# Rev_1.net
KiCad netlist of a schematic drawn in EAGLE
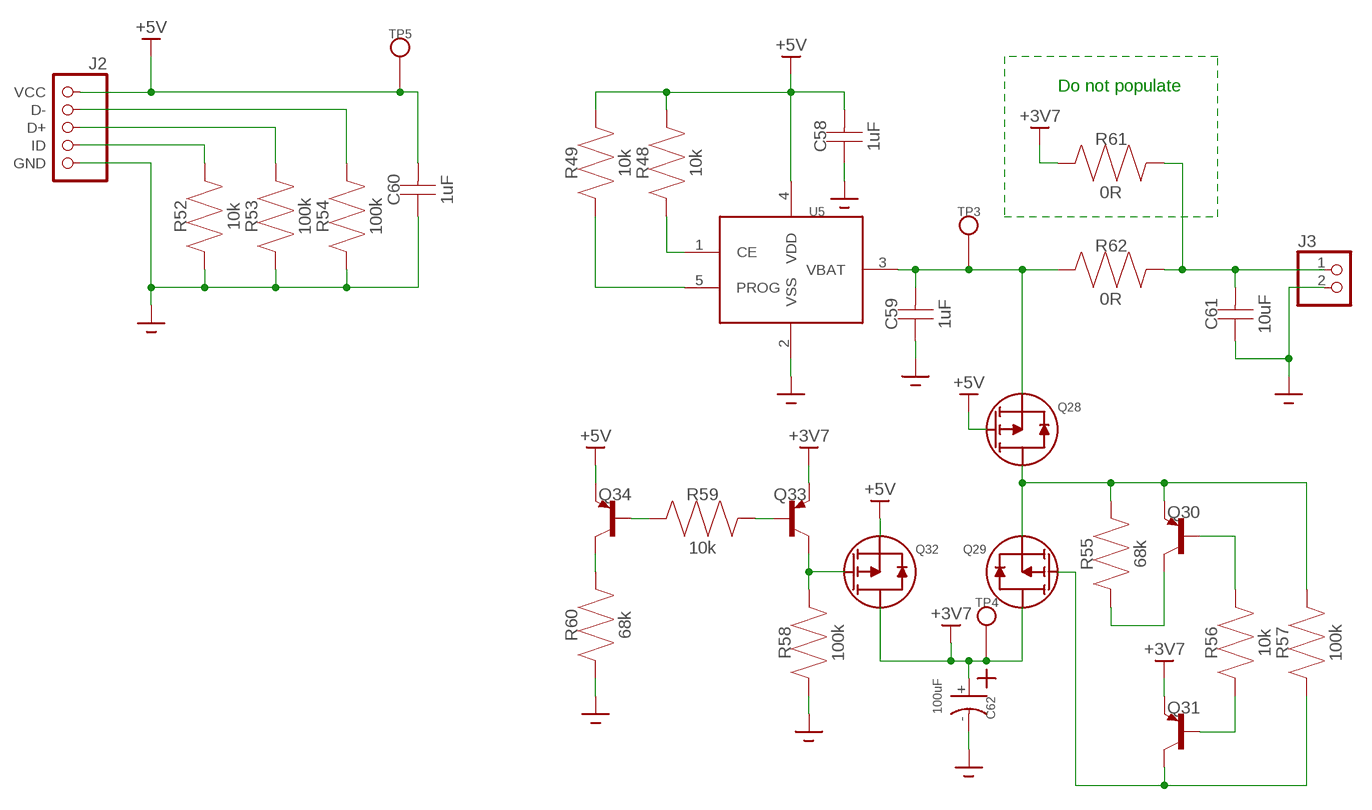
[diagram p0: schematic, sheet 1]
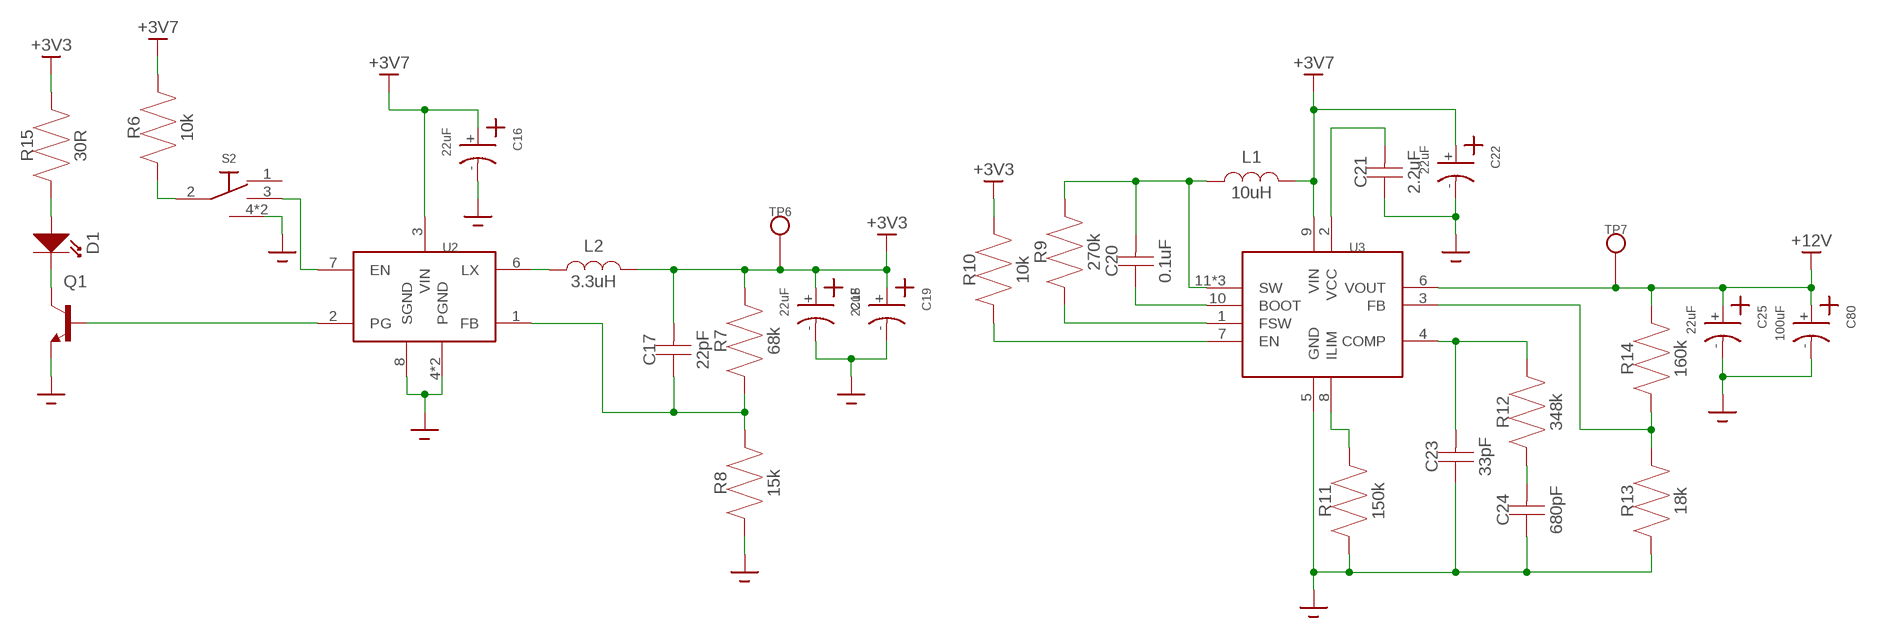
[diagram p1: schematic, sheet 2]
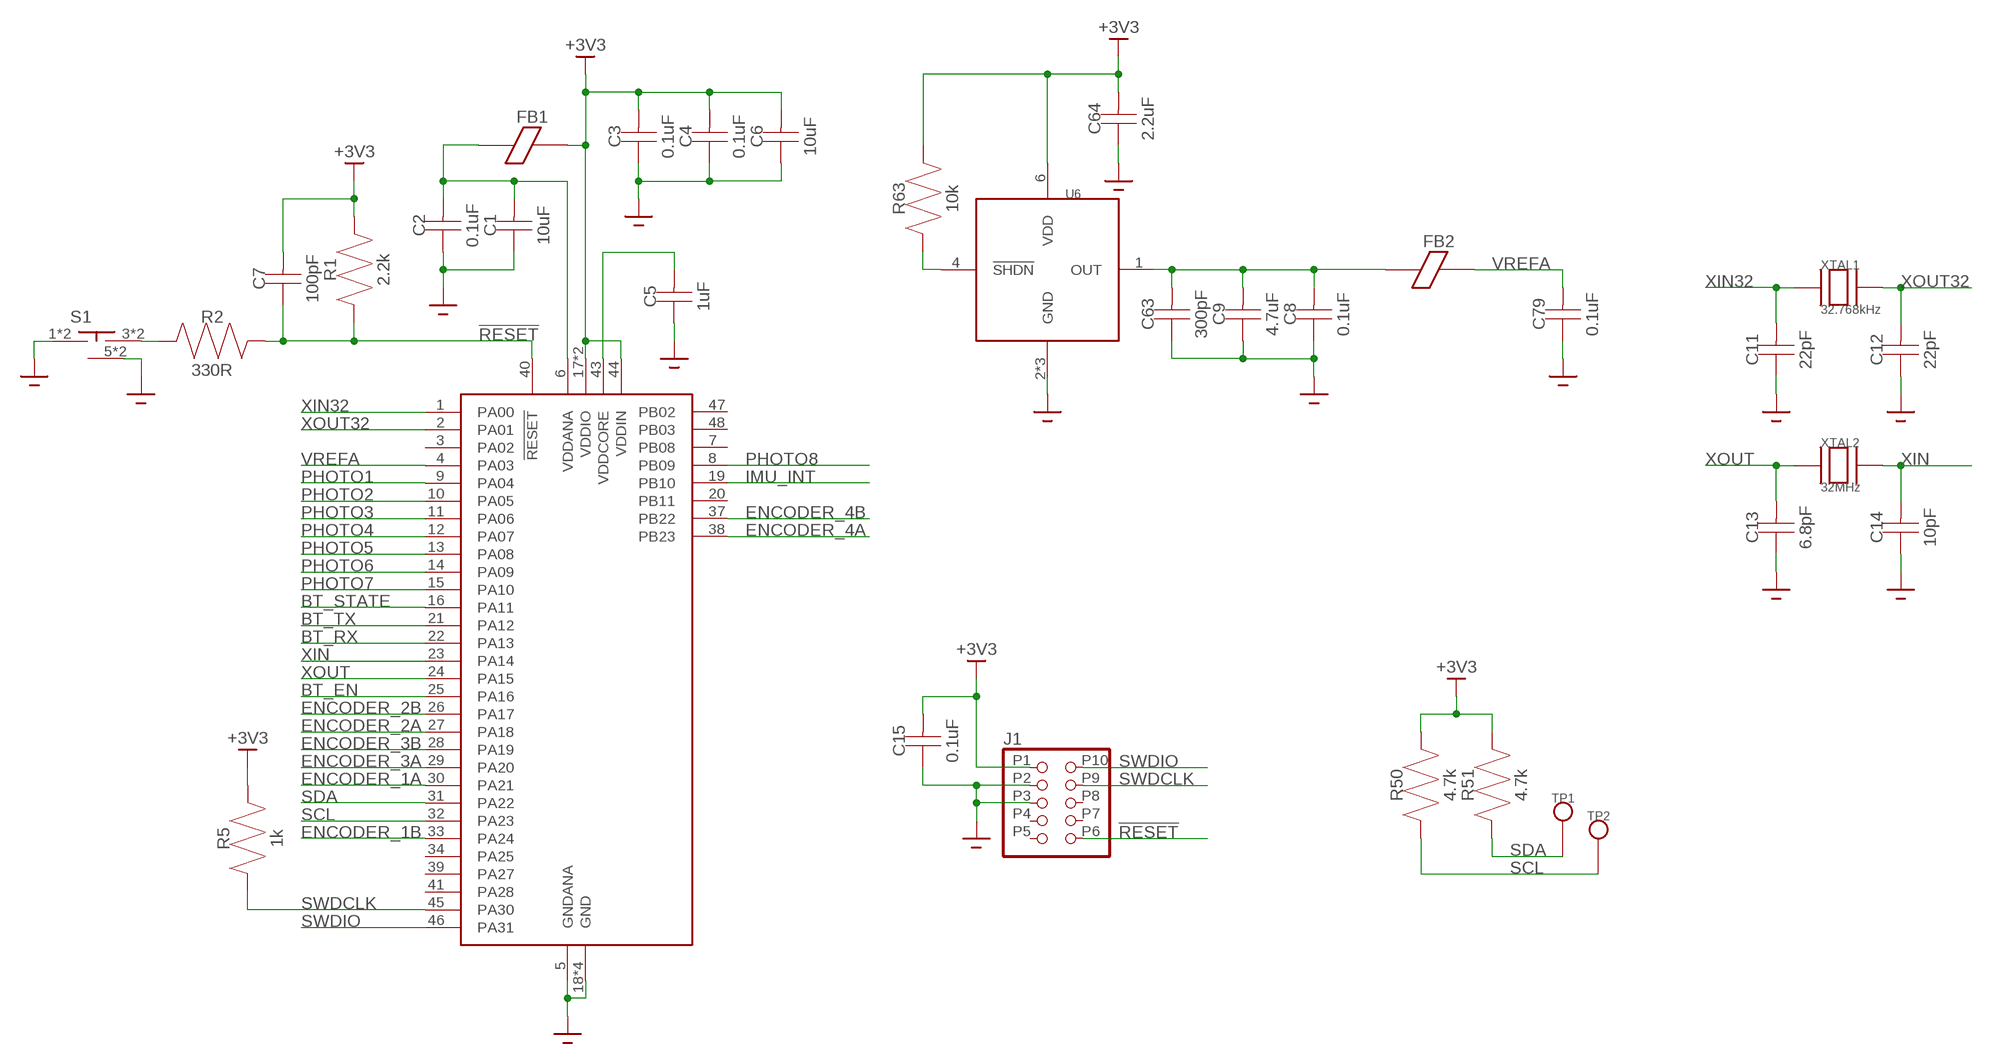
[diagram p2: schematic, sheet 3]
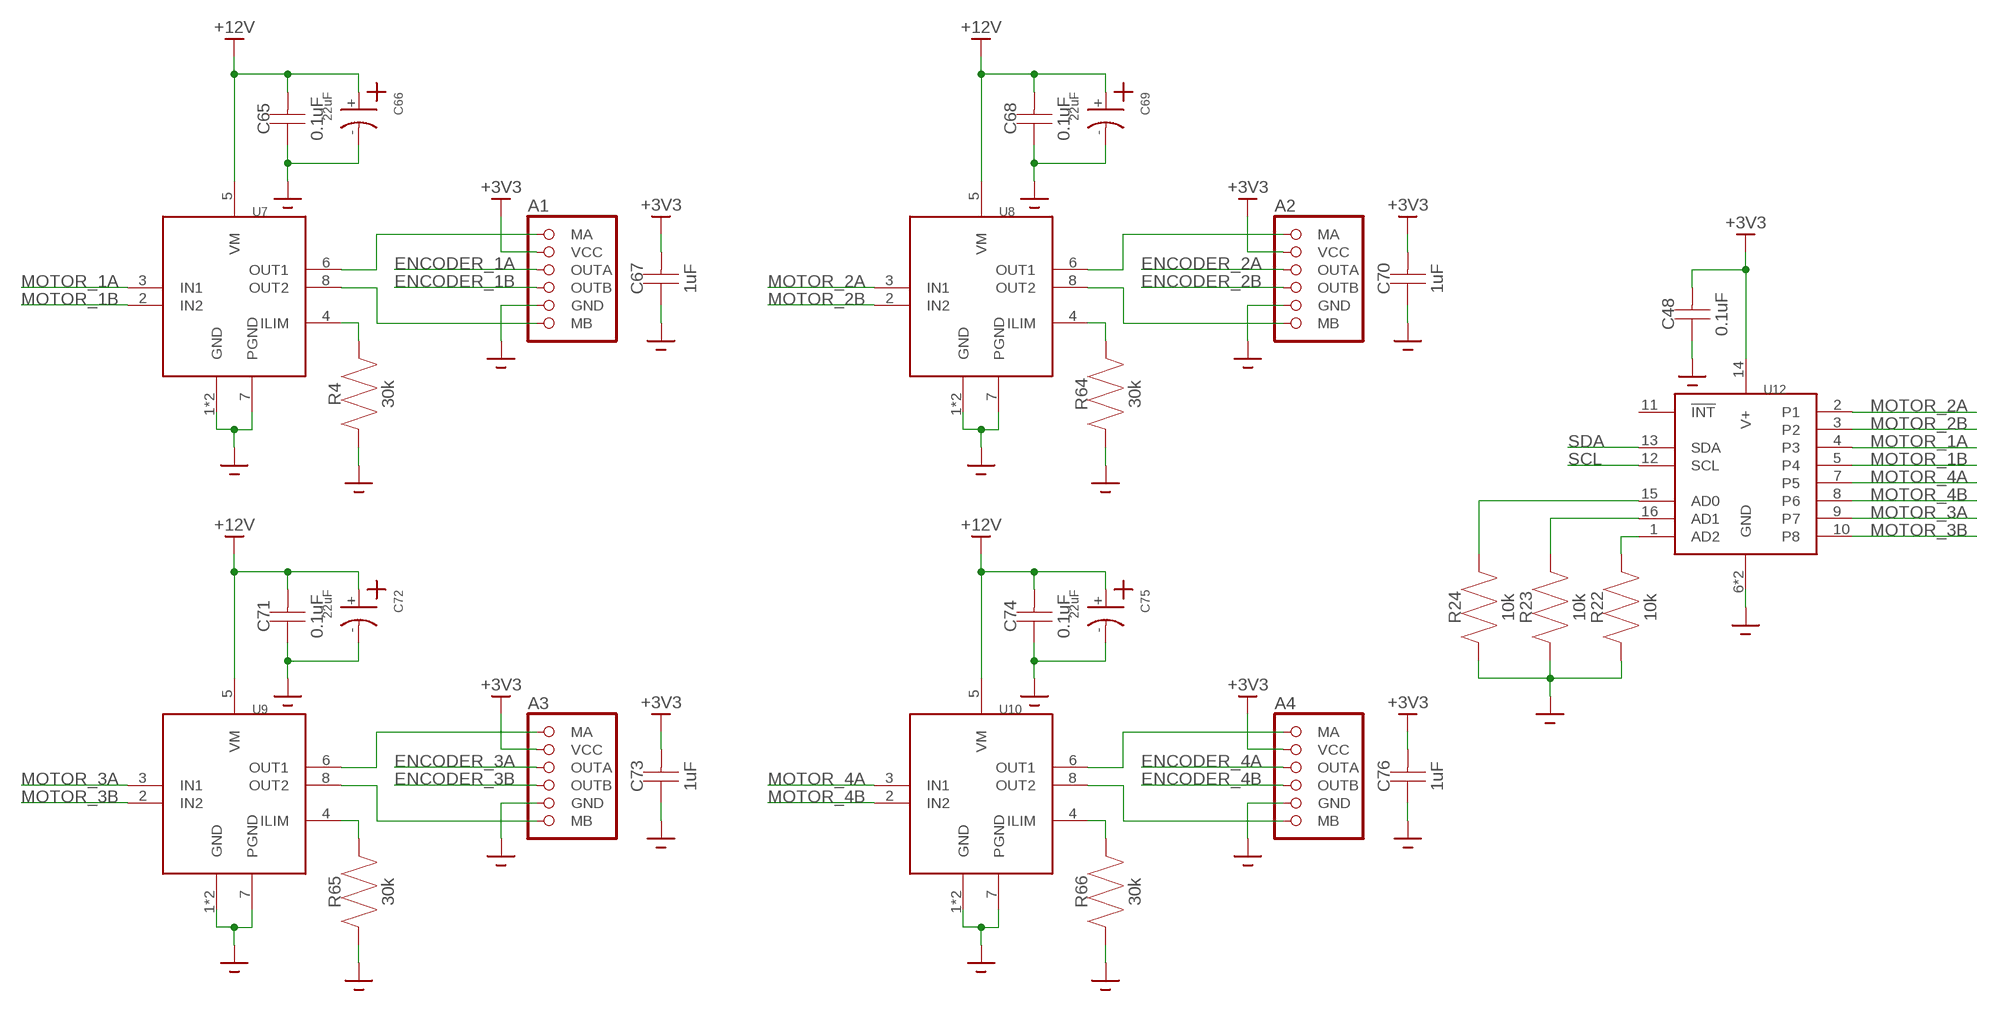
[diagram p3: schematic, sheet 4]
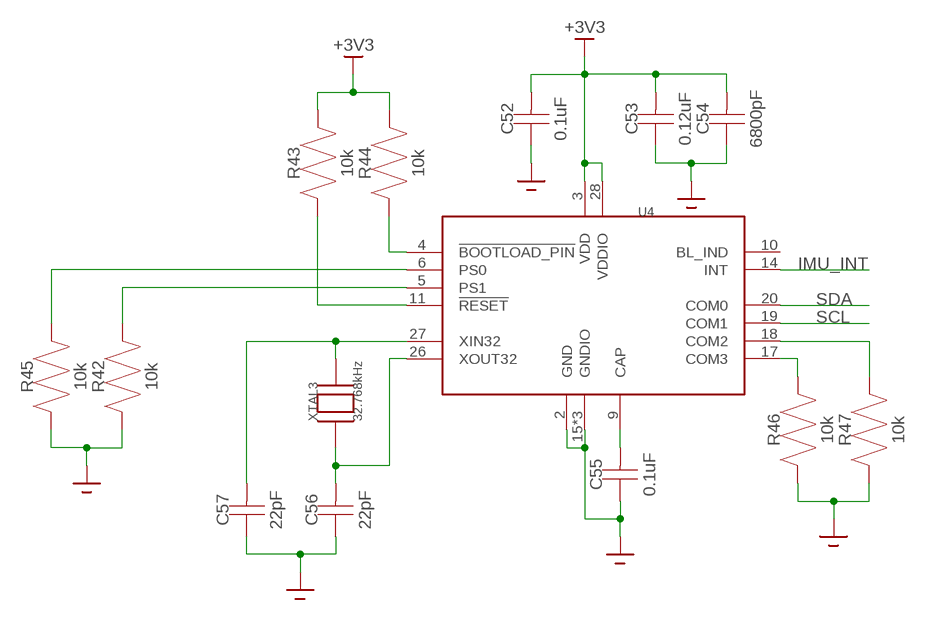
[diagram p4: schematic, sheet 5]
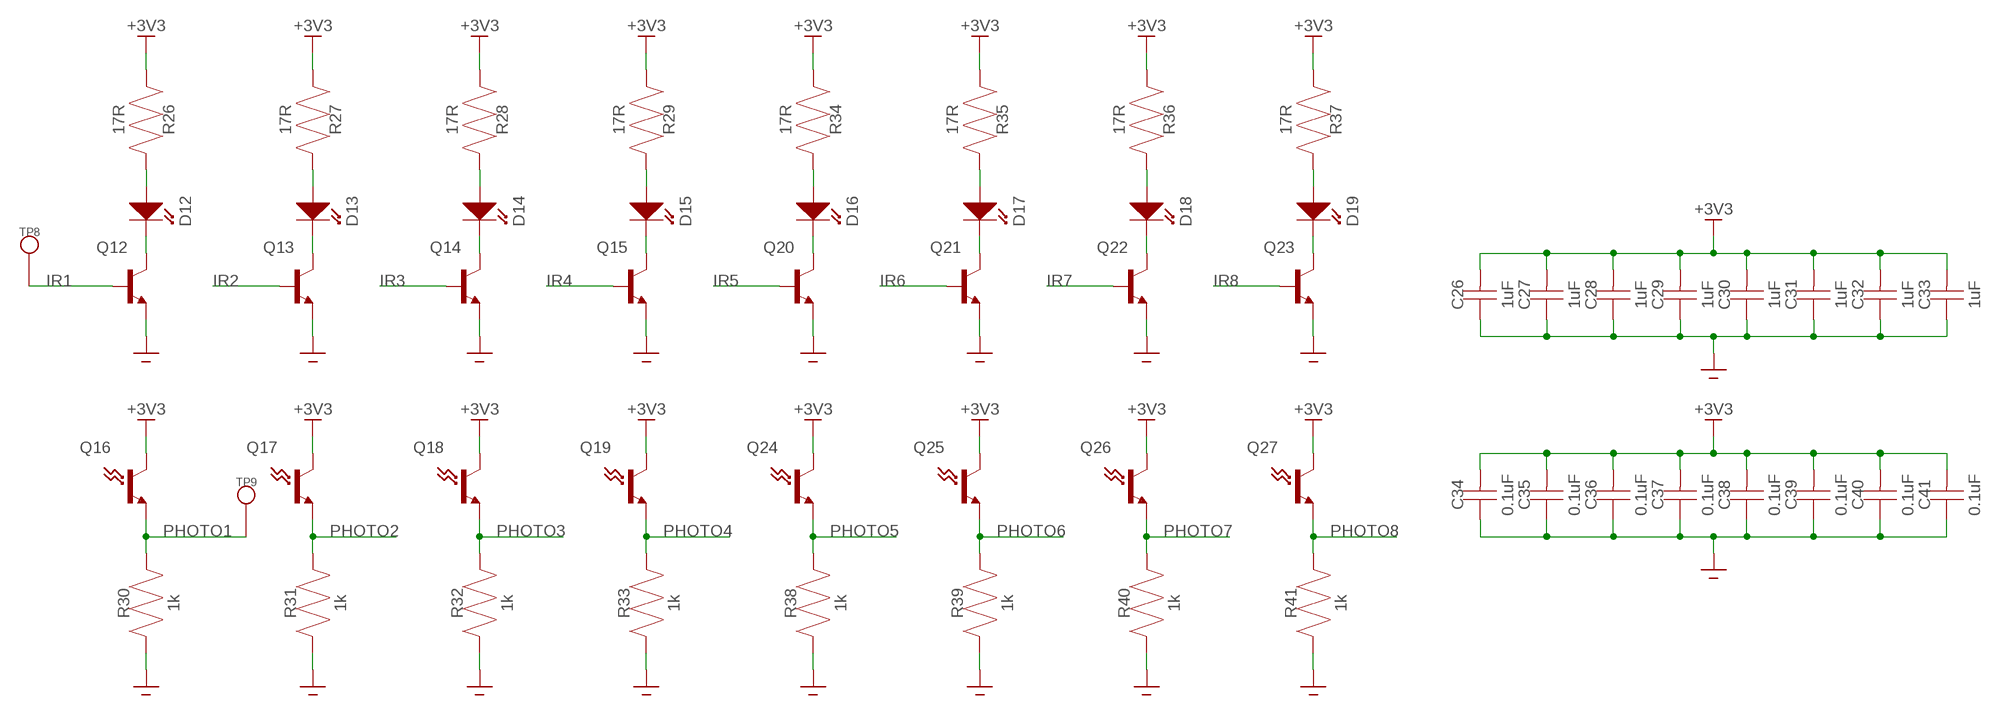
[diagram p5: schematic, sheet 6]
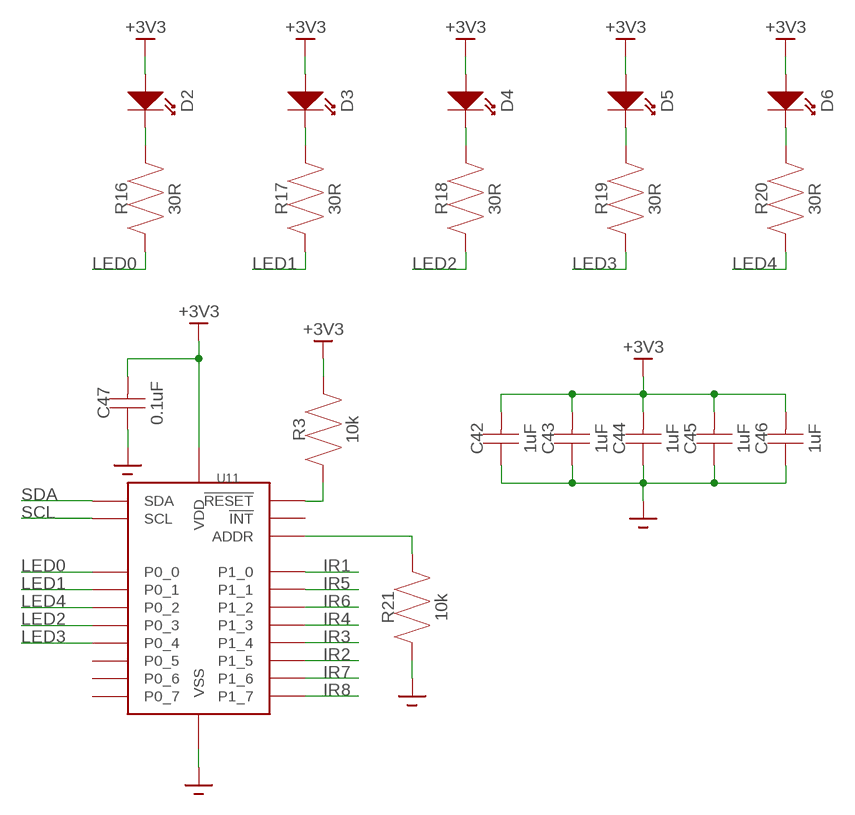
[diagram p6: schematic, sheet 7]
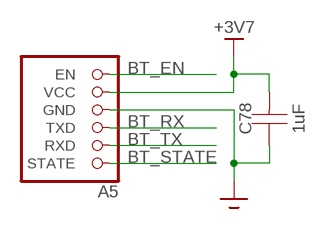
[diagram p7: schematic, sheet 8]

(export (version "E")
  (design (tool "Eeschema 10.0.6"))
  (components
    (comp (ref "C26")
      (value "1uF")
      (footprint "eagle-import:0805")
      (libsource (lib "eagle-import") (part "CAPACITOR0805"))
    )
    (comp (ref "C27")
      (value "1uF")
      (footprint "eagle-import:0805")
      (libsource (lib "eagle-import") (part "CAPACITOR0805"))
    )
    (comp (ref "C28")
      (value "1uF")
      (footprint "eagle-import:0805")
      (libsource (lib "eagle-import") (part "CAPACITOR0805"))
    )
    (comp (ref "C29")
      (value "1uF")
      (footprint "eagle-import:0805")
      (libsource (lib "eagle-import") (part "CAPACITOR0805"))
    )
    (comp (ref "C30")
      (value "1uF")
      (footprint "eagle-import:0805")
      (libsource (lib "eagle-import") (part "CAPACITOR0805"))
    )
    (comp (ref "C31")
      (value "1uF")
      (footprint "eagle-import:0805")
      (libsource (lib "eagle-import") (part "CAPACITOR0805"))
    )
    (comp (ref "C32")
      (value "1uF")
      (footprint "eagle-import:0805")
      (libsource (lib "eagle-import") (part "CAPACITOR0805"))
    )
    (comp (ref "C33")
      (value "1uF")
      (footprint "eagle-import:0603")
      (libsource (lib "eagle-import") (part "CAPACITOR0603"))
    )
    (comp (ref "C34")
      (value "0.1uF")
      (footprint "eagle-import:0805")
      (libsource (lib "eagle-import") (part "CAPACITOR0805"))
    )
    (comp (ref "C35")
      (value "0.1uF")
      (footprint "eagle-import:0805")
      (libsource (lib "eagle-import") (part "CAPACITOR0805"))
    )
    (comp (ref "C36")
      (value "0.1uF")
      (footprint "eagle-import:0805")
      (libsource (lib "eagle-import") (part "CAPACITOR0805"))
    )
    (comp (ref "C37")
      (value "0.1uF")
      (footprint "eagle-import:0805")
      (libsource (lib "eagle-import") (part "CAPACITOR0805"))
    )
    (comp (ref "C38")
      (value "0.1uF")
      (footprint "eagle-import:0805")
      (libsource (lib "eagle-import") (part "CAPACITOR0805"))
    )
    (comp (ref "C39")
      (value "0.1uF")
      (footprint "eagle-import:0805")
      (libsource (lib "eagle-import") (part "CAPACITOR0805"))
    )
    (comp (ref "C40")
      (value "0.1uF")
      (footprint "eagle-import:0603")
      (libsource (lib "eagle-import") (part "CAPACITOR0603"))
    )
    (comp (ref "C41")
      (value "0.1uF")
      (footprint "eagle-import:0805")
      (libsource (lib "eagle-import") (part "CAPACITOR0805"))
    )
    (comp (ref "D12")
      (value "SFH4545")
      (footprint "eagle-import:SFH4545")
      (libsource (lib "eagle-import") (part "SFH4545"))
    )
    (comp (ref "D13")
      (value "SFH4545")
      (footprint "eagle-import:SFH4545")
      (libsource (lib "eagle-import") (part "SFH4545"))
    )
    (comp (ref "D14")
      (value "SFH4545")
      (footprint "eagle-import:SFH4545")
      (libsource (lib "eagle-import") (part "SFH4545"))
    )
    (comp (ref "D15")
      (value "SFH4545")
      (footprint "eagle-import:SFH4545")
      (libsource (lib "eagle-import") (part "SFH4545"))
    )
    (comp (ref "D16")
      (value "SFH4545")
      (footprint "eagle-import:SFH4545")
      (libsource (lib "eagle-import") (part "SFH4545"))
    )
    (comp (ref "D17")
      (value "SFH4545")
      (footprint "eagle-import:SFH4545")
      (libsource (lib "eagle-import") (part "SFH4545"))
    )
    (comp (ref "D18")
      (value "SFH4545")
      (footprint "eagle-import:SFH4545")
      (libsource (lib "eagle-import") (part "SFH4545"))
    )
    (comp (ref "D19")
      (value "SFH4545")
      (footprint "eagle-import:SFH4545")
      (libsource (lib "eagle-import") (part "SFH4545"))
    )
    (comp (ref "Q12")
      (value "MMBT3904,215MMBT3904,215")
      (footprint "eagle-import:SOT95P230X110-3")
      (libsource (lib "eagle-import") (part "MMBT3904,215MMBT3904,215"))
    )
    (comp (ref "Q13")
      (value "MMBT3904,215MMBT3904,215")
      (footprint "eagle-import:SOT95P230X110-3")
      (libsource (lib "eagle-import") (part "MMBT3904,215MMBT3904,215"))
    )
    (comp (ref "Q14")
      (value "MMBT3904,215MMBT3904,215")
      (footprint "eagle-import:SOT95P230X110-3")
      (libsource (lib "eagle-import") (part "MMBT3904,215MMBT3904,215"))
    )
    (comp (ref "Q15")
      (value "MMBT3904,215MMBT3904,215")
      (footprint "eagle-import:SOT95P230X110-3")
      (libsource (lib "eagle-import") (part "MMBT3904,215MMBT3904,215"))
    )
    (comp (ref "Q16")
      (value "TEFT4300")
      (footprint "eagle-import:TEFT4300")
      (libsource (lib "eagle-import") (part "TEFT4300"))
    )
    (comp (ref "Q17")
      (value "TEFT4300")
      (footprint "eagle-import:TEFT4300")
      (libsource (lib "eagle-import") (part "TEFT4300"))
    )
    (comp (ref "Q18")
      (value "TEFT4300")
      (footprint "eagle-import:TEFT4300")
      (libsource (lib "eagle-import") (part "TEFT4300"))
    )
    (comp (ref "Q19")
      (value "TEFT4300")
      (footprint "eagle-import:TEFT4300")
      (libsource (lib "eagle-import") (part "TEFT4300"))
    )
    (comp (ref "Q20")
      (value "MMBT3904,215MMBT3904,215")
      (footprint "eagle-import:SOT95P230X110-3")
      (libsource (lib "eagle-import") (part "MMBT3904,215MMBT3904,215"))
    )
    (comp (ref "Q21")
      (value "MMBT3904,215MMBT3904,215")
      (footprint "eagle-import:SOT95P230X110-3")
      (libsource (lib "eagle-import") (part "MMBT3904,215MMBT3904,215"))
    )
    (comp (ref "Q22")
      (value "MMBT3904,215MMBT3904,215")
      (footprint "eagle-import:SOT95P230X110-3")
      (libsource (lib "eagle-import") (part "MMBT3904,215MMBT3904,215"))
    )
    (comp (ref "Q23")
      (value "MMBT3904,215MMBT3904,215")
      (footprint "eagle-import:SOT95P230X110-3")
      (libsource (lib "eagle-import") (part "MMBT3904,215MMBT3904,215"))
    )
    (comp (ref "Q24")
      (value "TEFT4300")
      (footprint "eagle-import:TEFT4300")
      (libsource (lib "eagle-import") (part "TEFT4300"))
    )
    (comp (ref "Q25")
      (value "TEFT4300")
      (footprint "eagle-import:TEFT4300")
      (libsource (lib "eagle-import") (part "TEFT4300"))
    )
    (comp (ref "Q26")
      (value "TEFT4300")
      (footprint "eagle-import:TEFT4300")
      (libsource (lib "eagle-import") (part "TEFT4300"))
    )
    (comp (ref "Q27")
      (value "TEFT4300")
      (footprint "eagle-import:TEFT4300")
      (libsource (lib "eagle-import") (part "TEFT4300"))
    )
    (comp (ref "R26")
      (value "17R")
      (footprint "eagle-import:0805")
      (libsource (lib "eagle-import") (part "RESISTOR0805"))
    )
    (comp (ref "R27")
      (value "17R")
      (footprint "eagle-import:0805")
      (libsource (lib "eagle-import") (part "RESISTOR0805"))
    )
    (comp (ref "R28")
      (value "17R")
      (footprint "eagle-import:0805")
      (libsource (lib "eagle-import") (part "RESISTOR0805"))
    )
    (comp (ref "R29")
      (value "17R")
      (footprint "eagle-import:0805")
      (libsource (lib "eagle-import") (part "RESISTOR0805"))
    )
    (comp (ref "R30")
      (value "1k")
      (footprint "eagle-import:0805")
      (libsource (lib "eagle-import") (part "RESISTOR0805"))
    )
    (comp (ref "R31")
      (value "1k")
      (footprint "eagle-import:0805")
      (libsource (lib "eagle-import") (part "RESISTOR0805"))
    )
    (comp (ref "R32")
      (value "1k")
      (footprint "eagle-import:0805")
      (libsource (lib "eagle-import") (part "RESISTOR0805"))
    )
    (comp (ref "R33")
      (value "1k")
      (footprint "eagle-import:0805")
      (libsource (lib "eagle-import") (part "RESISTOR0805"))
    )
    (comp (ref "R34")
      (value "17R")
      (footprint "eagle-import:0805")
      (libsource (lib "eagle-import") (part "RESISTOR0805"))
    )
    (comp (ref "R35")
      (value "17R")
      (footprint "eagle-import:0805")
      (libsource (lib "eagle-import") (part "RESISTOR0805"))
    )
    (comp (ref "R36")
      (value "17R")
      (footprint "eagle-import:0805")
      (libsource (lib "eagle-import") (part "RESISTOR0805"))
    )
    (comp (ref "R37")
      (value "17R")
      (footprint "eagle-import:0805")
      (libsource (lib "eagle-import") (part "RESISTOR0805"))
    )
    (comp (ref "R38")
      (value "1k")
      (footprint "eagle-import:0805")
      (libsource (lib "eagle-import") (part "RESISTOR0805"))
    )
    (comp (ref "R39")
      (value "1k")
      (footprint "eagle-import:0805")
      (libsource (lib "eagle-import") (part "RESISTOR0805"))
    )
    (comp (ref "R40")
      (value "1k")
      (footprint "eagle-import:0603")
      (libsource (lib "eagle-import") (part "RESISTOR0603"))
    )
    (comp (ref "R41")
      (value "1k")
      (footprint "eagle-import:0805")
      (libsource (lib "eagle-import") (part "RESISTOR0805"))
    )
    (comp (ref "TP8")
      (value "TESTPOINT")
      (footprint "eagle-import:TESTPOINT")
      (libsource (lib "eagle-import") (part "TESTPOINT"))
    )
    (comp (ref "TP9")
      (value "TESTPOINT")
      (footprint "eagle-import:TESTPOINT")
      (libsource (lib "eagle-import") (part "TESTPOINT"))
    )
    (comp (ref "C1")
      (value "10uF")
      (footprint "eagle-import:0402")
      (libsource (lib "eagle-import") (part "CAPACITOR0402"))
    )
    (comp (ref "C2")
      (value "0.1uF")
      (footprint "eagle-import:0402")
      (libsource (lib "eagle-import") (part "CAPACITOR0402"))
    )
    (comp (ref "C3")
      (value "0.1uF")
      (footprint "eagle-import:0402")
      (libsource (lib "eagle-import") (part "CAPACITOR0402"))
    )
    (comp (ref "C4")
      (value "0.1uF")
      (footprint "eagle-import:0402")
      (libsource (lib "eagle-import") (part "CAPACITOR0402"))
    )
    (comp (ref "C5")
      (value "1uF")
      (footprint "eagle-import:0402")
      (libsource (lib "eagle-import") (part "CAPACITOR0402"))
    )
    (comp (ref "C6")
      (value "10uF")
      (footprint "eagle-import:0402")
      (libsource (lib "eagle-import") (part "CAPACITOR0402"))
    )
    (comp (ref "C7")
      (value "100pF")
      (footprint "eagle-import:0603")
      (libsource (lib "eagle-import") (part "CAPACITOR0603"))
    )
    (comp (ref "C8")
      (value "0.1uF")
      (footprint "eagle-import:0402")
      (libsource (lib "eagle-import") (part "CAPACITOR0402"))
    )
    (comp (ref "C9")
      (value "4.7uF")
      (footprint "eagle-import:0402")
      (libsource (lib "eagle-import") (part "CAPACITOR0402"))
    )
    (comp (ref "C11")
      (value "22pF")
      (footprint "eagle-import:0402")
      (libsource (lib "eagle-import") (part "CAPACITOR0402"))
    )
    (comp (ref "C12")
      (value "22pF")
      (footprint "eagle-import:0402")
      (libsource (lib "eagle-import") (part "CAPACITOR0402"))
    )
    (comp (ref "C13")
      (value "6.8pF")
      (footprint "eagle-import:0402")
      (libsource (lib "eagle-import") (part "CAPACITOR0402"))
    )
    (comp (ref "C14")
      (value "10pF")
      (footprint "eagle-import:0402")
      (libsource (lib "eagle-import") (part "CAPACITOR0402"))
    )
    (comp (ref "C15")
      (value "0.1uF")
      (footprint "eagle-import:0603")
      (libsource (lib "eagle-import") (part "CAPACITOR0603"))
    )
    (comp (ref "C63")
      (value "300pF")
      (footprint "eagle-import:0402")
      (libsource (lib "eagle-import") (part "CAPACITOR0402"))
    )
    (comp (ref "C64")
      (value "2.2uF")
      (footprint "eagle-import:0402")
      (libsource (lib "eagle-import") (part "CAPACITOR0402"))
    )
    (comp (ref "C79")
      (value "0.1uF")
      (footprint "eagle-import:0402")
      (libsource (lib "eagle-import") (part "CAPACITOR0402"))
    )
    (comp (ref "FB1")
      (value "FERRITE0402")
      (footprint "eagle-import:0402")
      (libsource (lib "eagle-import") (part "FERRITE0402"))
    )
    (comp (ref "FB2")
      (value "FERRITE0402")
      (footprint "eagle-import:0402")
      (libsource (lib "eagle-import") (part "FERRITE0402"))
    )
    (comp (ref "J1")
      (value "3220-10-0100-00")
      (footprint "eagle-import:3220-10-0100-00")
      (libsource (lib "eagle-import") (part "3220-10-0100-00"))
    )
    (comp (ref "R1")
      (value "2.2k")
      (footprint "eagle-import:0603")
      (libsource (lib "eagle-import") (part "RESISTOR0603"))
    )
    (comp (ref "R2")
      (value "330R")
      (footprint "eagle-import:0805")
      (libsource (lib "eagle-import") (part "RESISTOR0805"))
    )
    (comp (ref "R5")
      (value "1k")
      (footprint "eagle-import:0603")
      (libsource (lib "eagle-import") (part "RESISTOR0603"))
    )
    (comp (ref "R50")
      (value "4.7k")
      (footprint "eagle-import:0603")
      (libsource (lib "eagle-import") (part "RESISTOR0603"))
    )
    (comp (ref "R51")
      (value "4.7k")
      (footprint "eagle-import:0603")
      (libsource (lib "eagle-import") (part "RESISTOR0603"))
    )
    (comp (ref "R63")
      (value "10k")
      (footprint "eagle-import:0402")
      (libsource (lib "eagle-import") (part "RESISTOR0402"))
    )
    (comp (ref "S1")
      (value "PTS526SMG15SMTR2LFS")
      (footprint "eagle-import:PTS526SMG15SMTR2LFS")
      (libsource (lib "eagle-import") (part "PTS526SMG15SMTR2LFS"))
    )
    (comp (ref "TP1")
      (value "TESTPOINT")
      (footprint "eagle-import:TESTPOINT")
      (libsource (lib "eagle-import") (part "TESTPOINT"))
    )
    (comp (ref "TP2")
      (value "TESTPOINT")
      (footprint "eagle-import:TESTPOINT")
      (libsource (lib "eagle-import") (part "TESTPOINT"))
    )
    (comp (ref "U1")
      (value "ATSAMD21G18A-MU")
      (footprint "eagle-import:ATSAMD21G18A-MU")
      (libsource (lib "eagle-import") (part "ATSAMD21G18A-MU"))
    )
    (comp (ref "U6")
      (value "MCP1501")
      (footprint "eagle-import:MCP1501")
      (libsource (lib "eagle-import") (part "MCP1501"))
    )
    (comp (ref "XTAL1")
      (value "32.768kHz")
      (footprint "eagle-import:FC-135")
      (libsource (lib "eagle-import") (part "FC-135"))
    )
    (comp (ref "XTAL2")
      (value "32MHz")
      (footprint "eagle-import:XRCGB")
      (libsource (lib "eagle-import") (part "XRCGB"))
    )
    (comp (ref "C52")
      (value "0.1uF")
      (footprint "eagle-import:0603")
      (libsource (lib "eagle-import") (part "CAPACITOR0603"))
    )
    (comp (ref "C53")
      (value "0.12uF")
      (footprint "eagle-import:0603")
      (libsource (lib "eagle-import") (part "CAPACITOR0603"))
    )
    (comp (ref "C54")
      (value "6800pF")
      (footprint "eagle-import:0603")
      (libsource (lib "eagle-import") (part "CAPACITOR0603"))
    )
    (comp (ref "C55")
      (value "0.1uF")
      (footprint "eagle-import:0603")
      (libsource (lib "eagle-import") (part "CAPACITOR0603"))
    )
    (comp (ref "C56")
      (value "22pF")
      (footprint "eagle-import:0603")
      (libsource (lib "eagle-import") (part "CAPACITOR0603"))
    )
    (comp (ref "C57")
      (value "22pF")
      (footprint "eagle-import:0603")
      (libsource (lib "eagle-import") (part "CAPACITOR0603"))
    )
    (comp (ref "R42")
      (value "10k")
      (footprint "eagle-import:0603")
      (libsource (lib "eagle-import") (part "RESISTOR0603"))
    )
    (comp (ref "R43")
      (value "10k")
      (footprint "eagle-import:0603")
      (libsource (lib "eagle-import") (part "RESISTOR0603"))
    )
    (comp (ref "R44")
      (value "10k")
      (footprint "eagle-import:0603")
      (libsource (lib "eagle-import") (part "RESISTOR0603"))
    )
    (comp (ref "R45")
      (value "10k")
      (footprint "eagle-import:0603")
      (libsource (lib "eagle-import") (part "RESISTOR0603"))
    )
    (comp (ref "R46")
      (value "10k")
      (footprint "eagle-import:0603")
      (libsource (lib "eagle-import") (part "RESISTOR0603"))
    )
    (comp (ref "R47")
      (value "10k")
      (footprint "eagle-import:0603")
      (libsource (lib "eagle-import") (part "RESISTOR0603"))
    )
    (comp (ref "U4")
      (value "BNO055")
      (footprint "eagle-import:BNO055")
      (libsource (lib "eagle-import") (part "BNO055"))
    )
    (comp (ref "XTAL3")
      (value "32.768kHz")
      (footprint "eagle-import:FC-135")
      (libsource (lib "eagle-import") (part "FC-135"))
    )
    (comp (ref "A1")
      (value "ENCODERSLOT")
      (footprint "eagle-import:ENCODER-SLOT")
      (libsource (lib "eagle-import") (part "ENCODERSLOT"))
    )
    (comp (ref "A2")
      (value "ENCODERSLOT")
      (footprint "eagle-import:ENCODER-SLOT")
      (libsource (lib "eagle-import") (part "ENCODERSLOT"))
    )
    (comp (ref "A3")
      (value "ENCODERSLOT")
      (footprint "eagle-import:ENCODER-SLOT")
      (libsource (lib "eagle-import") (part "ENCODERSLOT"))
    )
    (comp (ref "A4")
      (value "ENCODERSLOT")
      (footprint "eagle-import:ENCODER-SLOT")
      (libsource (lib "eagle-import") (part "ENCODERSLOT"))
    )
    (comp (ref "C48")
      (value "0.1uF")
      (footprint "eagle-import:0603")
      (libsource (lib "eagle-import") (part "CAPACITOR0603"))
    )
    (comp (ref "C65")
      (value "0.1uF")
      (footprint "eagle-import:0805")
      (libsource (lib "eagle-import") (part "CAPACITOR0805"))
    )
    (comp (ref "C66")
      (value "22uF")
      (footprint "eagle-import:865080542006")
      (libsource (lib "eagle-import") (part "865080542006"))
    )
    (comp (ref "C67")
      (value "1uF")
      (footprint "eagle-import:0805")
      (libsource (lib "eagle-import") (part "CAPACITOR0805"))
    )
    (comp (ref "C68")
      (value "0.1uF")
      (footprint "eagle-import:0805")
      (libsource (lib "eagle-import") (part "CAPACITOR0805"))
    )
    (comp (ref "C69")
      (value "22uF")
      (footprint "eagle-import:865080542006")
      (libsource (lib "eagle-import") (part "865080542006"))
    )
    (comp (ref "C70")
      (value "1uF")
      (footprint "eagle-import:0805")
      (libsource (lib "eagle-import") (part "CAPACITOR0805"))
    )
    (comp (ref "C71")
      (value "0.1uF")
      (footprint "eagle-import:0805")
      (libsource (lib "eagle-import") (part "CAPACITOR0805"))
    )
    (comp (ref "C72")
      (value "22uF")
      (footprint "eagle-import:865080542006")
      (libsource (lib "eagle-import") (part "865080542006"))
    )
    (comp (ref "C73")
      (value "1uF")
      (footprint "eagle-import:0805")
      (libsource (lib "eagle-import") (part "CAPACITOR0805"))
    )
    (comp (ref "C74")
      (value "0.1uF")
      (footprint "eagle-import:0805")
      (libsource (lib "eagle-import") (part "CAPACITOR0805"))
    )
    (comp (ref "C75")
      (value "22uF")
      (footprint "eagle-import:865080542006")
      (libsource (lib "eagle-import") (part "865080542006"))
    )
    (comp (ref "C76")
      (value "1uF")
      (footprint "eagle-import:0805")
      (libsource (lib "eagle-import") (part "CAPACITOR0805"))
    )
    (comp (ref "R4")
      (value "30k")
      (footprint "eagle-import:0805")
      (libsource (lib "eagle-import") (part "RESISTOR0805"))
    )
    (comp (ref "R22")
      (value "10k")
      (footprint "eagle-import:0603")
      (libsource (lib "eagle-import") (part "RESISTOR0603"))
    )
    (comp (ref "R23")
      (value "10k")
      (footprint "eagle-import:0603")
      (libsource (lib "eagle-import") (part "RESISTOR0603"))
    )
    (comp (ref "R24")
      (value "10k")
      (footprint "eagle-import:0603")
      (libsource (lib "eagle-import") (part "RESISTOR0603"))
    )
    (comp (ref "R64")
      (value "30k")
      (footprint "eagle-import:0805")
      (libsource (lib "eagle-import") (part "RESISTOR0805"))
    )
    (comp (ref "R65")
      (value "30k")
      (footprint "eagle-import:0805")
      (libsource (lib "eagle-import") (part "RESISTOR0805"))
    )
    (comp (ref "R66")
      (value "30k")
      (footprint "eagle-import:0805")
      (libsource (lib "eagle-import") (part "RESISTOR0805"))
    )
    (comp (ref "U7")
      (value "DRV8871")
      (footprint "eagle-import:DRV8871")
      (libsource (lib "eagle-import") (part "DRV8871"))
    )
    (comp (ref "U8")
      (value "DRV8871")
      (footprint "eagle-import:DRV8871")
      (libsource (lib "eagle-import") (part "DRV8871"))
    )
    (comp (ref "U9")
      (value "DRV8871")
      (footprint "eagle-import:DRV8871")
      (libsource (lib "eagle-import") (part "DRV8871"))
    )
    (comp (ref "U10")
      (value "DRV8871")
      (footprint "eagle-import:DRV8871")
      (libsource (lib "eagle-import") (part "DRV8871"))
    )
    (comp (ref "U12")
      (value "MAX7315")
      (footprint "eagle-import:MAX7315")
      (libsource (lib "eagle-import") (part "MAX7315"))
    )
    (comp (ref "A5")
      (value "HC-05")
      (footprint "eagle-import:HC-05")
      (libsource (lib "eagle-import") (part "HC-05"))
    )
    (comp (ref "C78")
      (value "1uF")
      (footprint "eagle-import:0603")
      (libsource (lib "eagle-import") (part "CAPACITOR0603"))
    )
    (comp (ref "C42")
      (value "1uF")
      (footprint "eagle-import:0603")
      (libsource (lib "eagle-import") (part "CAPACITOR0603"))
    )
    (comp (ref "C43")
      (value "1uF")
      (footprint "eagle-import:0603")
      (libsource (lib "eagle-import") (part "CAPACITOR0603"))
    )
    (comp (ref "C44")
      (value "1uF")
      (footprint "eagle-import:0603")
      (libsource (lib "eagle-import") (part "CAPACITOR0603"))
    )
    (comp (ref "C45")
      (value "1uF")
      (footprint "eagle-import:0603")
      (libsource (lib "eagle-import") (part "CAPACITOR0603"))
    )
    (comp (ref "C46")
      (value "1uF")
      (footprint "eagle-import:0603")
      (libsource (lib "eagle-import") (part "CAPACITOR0603"))
    )
    (comp (ref "C47")
      (value "0.1uF")
      (footprint "eagle-import:0603")
      (libsource (lib "eagle-import") (part "CAPACITOR0603"))
    )
    (comp (ref "D2")
      (value "LED1206")
      (footprint "eagle-import:1206")
      (libsource (lib "eagle-import") (part "LED1206"))
    )
    (comp (ref "D3")
      (value "LED1206")
      (footprint "eagle-import:1206")
      (libsource (lib "eagle-import") (part "LED1206"))
    )
    (comp (ref "D4")
      (value "LED1206")
      (footprint "eagle-import:1206")
      (libsource (lib "eagle-import") (part "LED1206"))
    )
    (comp (ref "D5")
      (value "LED1206")
      (footprint "eagle-import:1206")
      (libsource (lib "eagle-import") (part "LED1206"))
    )
    (comp (ref "D6")
      (value "LED1206")
      (footprint "eagle-import:1206")
      (libsource (lib "eagle-import") (part "LED1206"))
    )
    (comp (ref "R3")
      (value "10k")
      (footprint "eagle-import:0603")
      (libsource (lib "eagle-import") (part "RESISTOR0603"))
    )
    (comp (ref "R16")
      (value "30R")
      (footprint "eagle-import:0603")
      (libsource (lib "eagle-import") (part "RESISTOR0603"))
    )
    (comp (ref "R17")
      (value "30R")
      (footprint "eagle-import:0603")
      (libsource (lib "eagle-import") (part "RESISTOR0603"))
    )
    (comp (ref "R18")
      (value "30R")
      (footprint "eagle-import:0603")
      (libsource (lib "eagle-import") (part "RESISTOR0603"))
    )
    (comp (ref "R19")
      (value "30R")
      (footprint "eagle-import:0603")
      (libsource (lib "eagle-import") (part "RESISTOR0603"))
    )
    (comp (ref "R20")
      (value "30R")
      (footprint "eagle-import:0603")
      (libsource (lib "eagle-import") (part "RESISTOR0603"))
    )
    (comp (ref "R21")
      (value "10k")
      (footprint "eagle-import:0603")
      (libsource (lib "eagle-import") (part "RESISTOR0603"))
    )
    (comp (ref "U11")
      (value "PCAL6416A")
      (footprint "eagle-import:PCAL6416A")
      (libsource (lib "eagle-import") (part "PCAL6416A"))
    )
    (comp (ref "C16")
      (value "22uF")
      (footprint "eagle-import:865080542006")
      (libsource (lib "eagle-import") (part "865080542006"))
    )
    (comp (ref "C17")
      (value "22pF")
      (footprint "eagle-import:0805")
      (libsource (lib "eagle-import") (part "CAPACITOR0805"))
    )
    (comp (ref "C18")
      (value "22uF")
      (footprint "eagle-import:865080542006")
      (libsource (lib "eagle-import") (part "865080542006"))
    )
    (comp (ref "C19")
      (value "22uF")
      (footprint "eagle-import:865080542006")
      (libsource (lib "eagle-import") (part "865080542006"))
    )
    (comp (ref "C20")
      (value "0.1uF")
      (footprint "eagle-import:0402")
      (libsource (lib "eagle-import") (part "CAPACITOR0402"))
    )
    (comp (ref "C21")
      (value "2.2uF")
      (footprint "eagle-import:0402")
      (libsource (lib "eagle-import") (part "CAPACITOR0402"))
    )
    (comp (ref "C22")
      (value "22uF")
      (footprint "eagle-import:865080542006")
      (libsource (lib "eagle-import") (part "865080542006"))
    )
    (comp (ref "C23")
      (value "33pF")
      (footprint "eagle-import:0402")
      (libsource (lib "eagle-import") (part "CAPACITOR0402"))
    )
    (comp (ref "C24")
      (value "680pF")
      (footprint "eagle-import:0402")
      (libsource (lib "eagle-import") (part "CAPACITOR0402"))
    )
    (comp (ref "C25")
      (value "22uF")
      (footprint "eagle-import:865080542006")
      (libsource (lib "eagle-import") (part "865080542006"))
    )
    (comp (ref "C80")
      (value "100uF")
      (footprint "eagle-import:EEE-1EA101AP")
      (libsource (lib "eagle-import") (part "EEE-1EA101AP"))
    )
    (comp (ref "D1")
      (value "LED1206")
      (footprint "eagle-import:1206")
      (libsource (lib "eagle-import") (part "LED1206"))
    )
    (comp (ref "L1")
      (value "10uH")
      (footprint "eagle-import:104CDMCC")
      (libsource (lib "eagle-import") (part "104CDMCC"))
    )
    (comp (ref "L2")
      (value "3.3uH")
      (footprint "eagle-import:NRS5040")
      (libsource (lib "eagle-import") (part "NRS5040"))
    )
    (comp (ref "Q1")
      (value "MMBT3904,215MMBT3904,215")
      (footprint "eagle-import:SOT95P230X110-3")
      (libsource (lib "eagle-import") (part "MMBT3904,215MMBT3904,215"))
    )
    (comp (ref "R6")
      (value "10k")
      (footprint "eagle-import:0805")
      (libsource (lib "eagle-import") (part "RESISTOR0805"))
    )
    (comp (ref "R7")
      (value "68k")
      (footprint "eagle-import:0805")
      (libsource (lib "eagle-import") (part "RESISTOR0805"))
    )
    (comp (ref "R8")
      (value "15k")
      (footprint "eagle-import:0805")
      (libsource (lib "eagle-import") (part "RESISTOR0805"))
    )
    (comp (ref "R9")
      (value "270k")
      (footprint "eagle-import:0402")
      (libsource (lib "eagle-import") (part "RESISTOR0402"))
    )
    (comp (ref "R10")
      (value "10k")
      (footprint "eagle-import:0603")
      (libsource (lib "eagle-import") (part "RESISTOR0603"))
    )
    (comp (ref "R11")
      (value "150k")
      (footprint "eagle-import:0603")
      (libsource (lib "eagle-import") (part "RESISTOR0603"))
    )
    (comp (ref "R12")
      (value "348k")
      (footprint "eagle-import:0402")
      (libsource (lib "eagle-import") (part "RESISTOR0402"))
    )
    (comp (ref "R13")
      (value "18k")
      (footprint "eagle-import:0402")
      (libsource (lib "eagle-import") (part "RESISTOR0402"))
    )
    (comp (ref "R14")
      (value "160k")
      (footprint "eagle-import:0402")
      (libsource (lib "eagle-import") (part "RESISTOR0402"))
    )
    (comp (ref "R15")
      (value "30R")
      (footprint "eagle-import:0805")
      (libsource (lib "eagle-import") (part "RESISTOR0805"))
    )
    (comp (ref "S2")
      (value "OS102011MS2QN1")
      (footprint "eagle-import:OS102011MS2QN1")
      (libsource (lib "eagle-import") (part "OS102011MS2QN1"))
    )
    (comp (ref "TP6")
      (value "TESTPOINT")
      (footprint "eagle-import:TESTPOINT")
      (libsource (lib "eagle-import") (part "TESTPOINT"))
    )
    (comp (ref "TP7")
      (value "TESTPOINT")
      (footprint "eagle-import:TESTPOINT")
      (libsource (lib "eagle-import") (part "TESTPOINT"))
    )
    (comp (ref "U2")
      (value "AP3441")
      (footprint "eagle-import:AP3441")
      (libsource (lib "eagle-import") (part "AP3441"))
    )
    (comp (ref "U3")
      (value "TPS61089")
      (footprint "eagle-import:TPS61089")
      (libsource (lib "eagle-import") (part "TPS61089"))
    )
    (comp (ref "C58")
      (value "1uF")
      (footprint "eagle-import:0805")
      (libsource (lib "eagle-import") (part "CAPACITOR0805"))
    )
    (comp (ref "C59")
      (value "1uF")
      (footprint "eagle-import:0805")
      (libsource (lib "eagle-import") (part "CAPACITOR0805"))
    )
    (comp (ref "C60")
      (value "1uF")
      (footprint "eagle-import:0805")
      (libsource (lib "eagle-import") (part "CAPACITOR0805"))
    )
    (comp (ref "C61")
      (value "10uF")
      (footprint "eagle-import:0805")
      (libsource (lib "eagle-import") (part "CAPACITOR0805"))
    )
    (comp (ref "C62")
      (value "100uF")
      (footprint "eagle-import:EEE-1EA101AP")
      (libsource (lib "eagle-import") (part "EEE-1EA101AP"))
    )
    (comp (ref "J2")
      (value "10118194-0001LF")
      (footprint "eagle-import:10118194-0001LF")
      (libsource (lib "eagle-import") (part "10118194-0001LF"))
    )
    (comp (ref "J3")
      (value "B2B-PH-K-S(LF)(SN)")
      (footprint "eagle-import:B2B-PH-K-S(LF)(SN)")
      (libsource (lib "eagle-import") (part "B2B-PH-K-S(LF)(SN)"))
    )
    (comp (ref "Q28")
      (value "SI7157DP")
      (footprint "eagle-import:SI7157DP")
      (libsource (lib "eagle-import") (part "SI7157DP"))
    )
    (comp (ref "Q29")
      (value "SI7157DP")
      (footprint "eagle-import:SI7157DP")
      (libsource (lib "eagle-import") (part "SI7157DP"))
    )
    (comp (ref "Q30")
      (value "MMBT3906")
      (footprint "eagle-import:SOT96P237X112-3")
      (libsource (lib "eagle-import") (part "MMBT3906"))
    )
    (comp (ref "Q31")
      (value "MMBT3906")
      (footprint "eagle-import:SOT96P237X112-3")
      (libsource (lib "eagle-import") (part "MMBT3906"))
    )
    (comp (ref "Q32")
      (value "SI7157DP")
      (footprint "eagle-import:SI7157DP")
      (libsource (lib "eagle-import") (part "SI7157DP"))
    )
    (comp (ref "Q33")
      (value "MMBT3906")
      (footprint "eagle-import:SOT96P237X112-3")
      (libsource (lib "eagle-import") (part "MMBT3906"))
    )
    (comp (ref "Q34")
      (value "MMBT3906")
      (footprint "eagle-import:SOT96P237X112-3")
      (libsource (lib "eagle-import") (part "MMBT3906"))
    )
    (comp (ref "R48")
      (value "10k")
      (footprint "eagle-import:0402")
      (libsource (lib "eagle-import") (part "RESISTOR0402"))
    )
    (comp (ref "R49")
      (value "10k")
      (footprint "eagle-import:0402")
      (libsource (lib "eagle-import") (part "RESISTOR0402"))
    )
    (comp (ref "R52")
      (value "10k")
      (footprint "eagle-import:0402")
      (libsource (lib "eagle-import") (part "RESISTOR0402"))
    )
    (comp (ref "R53")
      (value "100k")
      (footprint "eagle-import:0402")
      (libsource (lib "eagle-import") (part "RESISTOR0402"))
    )
    (comp (ref "R54")
      (value "100k")
      (footprint "eagle-import:0402")
      (libsource (lib "eagle-import") (part "RESISTOR0402"))
    )
    (comp (ref "R55")
      (value "68k")
      (footprint "eagle-import:0603")
      (libsource (lib "eagle-import") (part "RESISTOR0603"))
    )
    (comp (ref "R56")
      (value "10k")
      (footprint "eagle-import:0603")
      (libsource (lib "eagle-import") (part "RESISTOR0603"))
    )
    (comp (ref "R57")
      (value "100k")
      (footprint "eagle-import:0603")
      (libsource (lib "eagle-import") (part "RESISTOR0603"))
    )
    (comp (ref "R58")
      (value "100k")
      (footprint "eagle-import:0805")
      (libsource (lib "eagle-import") (part "RESISTOR0805"))
    )
    (comp (ref "R59")
      (value "10k")
      (footprint "eagle-import:0805")
      (libsource (lib "eagle-import") (part "RESISTOR0805"))
    )
    (comp (ref "R60")
      (value "68k")
      (footprint "eagle-import:0805")
      (libsource (lib "eagle-import") (part "RESISTOR0805"))
    )
    (comp (ref "R61")
      (value "0R")
      (footprint "eagle-import:0805")
      (libsource (lib "eagle-import") (part "RESISTOR0805"))
    )
    (comp (ref "R62")
      (value "0R")
      (footprint "eagle-import:0805")
      (libsource (lib "eagle-import") (part "RESISTOR0805"))
    )
    (comp (ref "TP3")
      (value "TESTPOINT")
      (footprint "eagle-import:TESTPOINT")
      (libsource (lib "eagle-import") (part "TESTPOINT"))
    )
    (comp (ref "TP4")
      (value "TESTPOINT")
      (footprint "eagle-import:TESTPOINT")
      (libsource (lib "eagle-import") (part "TESTPOINT"))
    )
    (comp (ref "TP5")
      (value "TESTPOINT")
      (footprint "eagle-import:TESTPOINT")
      (libsource (lib "eagle-import") (part "TESTPOINT"))
    )
    (comp (ref "U5")
      (value "MCP73811")
      (footprint "eagle-import:MCP73811")
      (libsource (lib "eagle-import") (part "MCP73811"))
    )
  )
  (nets
    (net (code "1") (name "+3V3") (class "Default")
      (node (ref "A1") (pin "2") (pinfunction "VCC_2") (pintype "power_in"))
      (node (ref "A2") (pin "2") (pinfunction "VCC_2") (pintype "power_in"))
      (node (ref "A3") (pin "2") (pinfunction "VCC_2") (pintype "power_in"))
      (node (ref "A4") (pin "2") (pinfunction "VCC_2") (pintype "power_in"))
      (node (ref "C15") (pin "2") (pinfunction "P$2_2") (pintype "passive"))
      (node (ref "C17") (pin "P$2") (pinfunction "P$2_P$2") (pintype "passive"))
      (node (ref "C18") (pin "+") (pinfunction "+_+") (pintype "passive"))
      (node (ref "C19") (pin "+") (pinfunction "+_+") (pintype "passive"))
      (node (ref "C26") (pin "P$2") (pinfunction "P$2_P$2") (pintype "passive"))
      (node (ref "C27") (pin "P$2") (pinfunction "P$2_P$2") (pintype "passive"))
      (node (ref "C28") (pin "P$2") (pinfunction "P$2_P$2") (pintype "passive"))
      (node (ref "C29") (pin "P$2") (pinfunction "P$2_P$2") (pintype "passive"))
      (node (ref "C3") (pin "2") (pinfunction "P$2_2") (pintype "passive"))
      (node (ref "C30") (pin "P$2") (pinfunction "P$2_P$2") (pintype "passive"))
      (node (ref "C31") (pin "P$2") (pinfunction "P$2_P$2") (pintype "passive"))
      (node (ref "C32") (pin "P$2") (pinfunction "P$2_P$2") (pintype "passive"))
      (node (ref "C33") (pin "2") (pinfunction "P$2_2") (pintype "passive"))
      (node (ref "C34") (pin "P$2") (pinfunction "P$2_P$2") (pintype "passive"))
      (node (ref "C35") (pin "P$2") (pinfunction "P$2_P$2") (pintype "passive"))
      (node (ref "C36") (pin "P$2") (pinfunction "P$2_P$2") (pintype "passive"))
      (node (ref "C37") (pin "P$2") (pinfunction "P$2_P$2") (pintype "passive"))
      (node (ref "C38") (pin "P$2") (pinfunction "P$2_P$2") (pintype "passive"))
      (node (ref "C39") (pin "P$2") (pinfunction "P$2_P$2") (pintype "passive"))
      (node (ref "C4") (pin "2") (pinfunction "P$2_2") (pintype "passive"))
      (node (ref "C40") (pin "2") (pinfunction "P$2_2") (pintype "passive"))
      (node (ref "C41") (pin "P$2") (pinfunction "P$2_P$2") (pintype "passive"))
      (node (ref "C42") (pin "2") (pinfunction "P$2_2") (pintype "passive"))
      (node (ref "C43") (pin "2") (pinfunction "P$2_2") (pintype "passive"))
      (node (ref "C44") (pin "2") (pinfunction "P$2_2") (pintype "passive"))
      (node (ref "C45") (pin "2") (pinfunction "P$2_2") (pintype "passive"))
      (node (ref "C46") (pin "2") (pinfunction "P$2_2") (pintype "passive"))
      (node (ref "C47") (pin "2") (pinfunction "P$2_2") (pintype "passive"))
      (node (ref "C48") (pin "2") (pinfunction "P$2_2") (pintype "passive"))
      (node (ref "C52") (pin "2") (pinfunction "P$2_2") (pintype "passive"))
      (node (ref "C53") (pin "2") (pinfunction "P$2_2") (pintype "passive"))
      (node (ref "C54") (pin "2") (pinfunction "P$2_2") (pintype "passive"))
      (node (ref "C6") (pin "2") (pinfunction "P$2_2") (pintype "passive"))
      (node (ref "C64") (pin "2") (pinfunction "P$2_2") (pintype "passive"))
      (node (ref "C67") (pin "P$2") (pinfunction "P$2_P$2") (pintype "passive"))
      (node (ref "C7") (pin "2") (pinfunction "P$2_2") (pintype "passive"))
      (node (ref "C70") (pin "P$2") (pinfunction "P$2_P$2") (pintype "passive"))
      (node (ref "C73") (pin "P$2") (pinfunction "P$2_P$2") (pintype "passive"))
      (node (ref "C76") (pin "P$2") (pinfunction "P$2_P$2") (pintype "passive"))
      (node (ref "D2") (pin "1") (pinfunction "IN_1") (pintype "passive"))
      (node (ref "D3") (pin "1") (pinfunction "IN_1") (pintype "passive"))
      (node (ref "D4") (pin "1") (pinfunction "IN_1") (pintype "passive"))
      (node (ref "D5") (pin "1") (pinfunction "IN_1") (pintype "passive"))
      (node (ref "D6") (pin "1") (pinfunction "IN_1") (pintype "passive"))
      (node (ref "FB1") (pin "2") (pinfunction "P$2_2") (pintype "passive"))
      (node (ref "J1") (pin "P1") (pinfunction "1_P1") (pintype "passive"))
      (node (ref "L2") (pin "2") (pinfunction "P$2_2") (pintype "passive"))
      (node (ref "Q16") (pin "C") (pinfunction "C_C") (pintype "passive"))
      (node (ref "Q17") (pin "C") (pinfunction "C_C") (pintype "passive"))
      (node (ref "Q18") (pin "C") (pinfunction "C_C") (pintype "passive"))
      (node (ref "Q19") (pin "C") (pinfunction "C_C") (pintype "passive"))
      (node (ref "Q24") (pin "C") (pinfunction "C_C") (pintype "passive"))
      (node (ref "Q25") (pin "C") (pinfunction "C_C") (pintype "passive"))
      (node (ref "Q26") (pin "C") (pinfunction "C_C") (pintype "passive"))
      (node (ref "Q27") (pin "C") (pinfunction "C_C") (pintype "passive"))
      (node (ref "R1") (pin "2") (pinfunction "P$2_2") (pintype "passive"))
      (node (ref "R10") (pin "2") (pinfunction "P$2_2") (pintype "passive"))
      (node (ref "R15") (pin "P$2") (pinfunction "P$2_P$2") (pintype "passive"))
      (node (ref "R26") (pin "P$1") (pinfunction "P$1_P$1") (pintype "passive"))
      (node (ref "R27") (pin "P$1") (pinfunction "P$1_P$1") (pintype "passive"))
      (node (ref "R28") (pin "P$1") (pinfunction "P$1_P$1") (pintype "passive"))
      (node (ref "R29") (pin "P$1") (pinfunction "P$1_P$1") (pintype "passive"))
      (node (ref "R3") (pin "2") (pinfunction "P$2_2") (pintype "passive"))
      (node (ref "R34") (pin "P$1") (pinfunction "P$1_P$1") (pintype "passive"))
      (node (ref "R35") (pin "P$1") (pinfunction "P$1_P$1") (pintype "passive"))
      (node (ref "R36") (pin "P$1") (pinfunction "P$1_P$1") (pintype "passive"))
      (node (ref "R37") (pin "P$1") (pinfunction "P$1_P$1") (pintype "passive"))
      (node (ref "R43") (pin "2") (pinfunction "P$2_2") (pintype "passive"))
      (node (ref "R44") (pin "2") (pinfunction "P$2_2") (pintype "passive"))
      (node (ref "R5") (pin "2") (pinfunction "P$2_2") (pintype "passive"))
      (node (ref "R50") (pin "2") (pinfunction "P$2_2") (pintype "passive"))
      (node (ref "R51") (pin "2") (pinfunction "P$2_2") (pintype "passive"))
      (node (ref "R63") (pin "2") (pinfunction "P$2_2") (pintype "passive"))
      (node (ref "R7") (pin "P$2") (pinfunction "P$2_P$2") (pintype "passive"))
      (node (ref "TP6") (pin "P1") (pinfunction "P$1_P1") (pintype "passive"))
      (node (ref "U1") (pin "17") (pinfunction "VDDIO_17") (pintype "power_in"))
      (node (ref "U1") (pin "36") (pinfunction "VDDIO_36") (pintype "power_in"))
      (node (ref "U1") (pin "44") (pinfunction "VDDIN_44") (pintype "power_in"))
      (node (ref "U11") (pin "21") (pinfunction "VDD_21") (pintype "power_in"))
      (node (ref "U11") (pin "23") (pinfunction "VDD_23") (pintype "power_in"))
      (node (ref "U12") (pin "14") (pinfunction "V+_14") (pintype "power_in"))
      (node (ref "U4") (pin "28") (pinfunction "VDDIO_28") (pintype "power_in"))
      (node (ref "U4") (pin "3") (pinfunction "VDD_3") (pintype "power_in"))
      (node (ref "U6") (pin "6") (pinfunction "VDD_6") (pintype "power_in"))
    )
    (net (code "2") (name "+3V7") (class "Default")
      (node (ref "A5") (pin "5") (pinfunction "VCC_5") (pintype "power_in"))
      (node (ref "C16") (pin "+") (pinfunction "+_+") (pintype "passive"))
      (node (ref "C22") (pin "+") (pinfunction "+_+") (pintype "passive"))
      (node (ref "C62") (pin "+") (pinfunction "+_+") (pintype "passive"))
      (node (ref "C78") (pin "2") (pinfunction "P$2_2") (pintype "passive"))
      (node (ref "L1") (pin "2") (pinfunction "P$2_2") (pintype "passive"))
      (node (ref "Q29") (pin "10") (pinfunction "D_10") (pintype "bidirectional"))
      (node (ref "Q29") (pin "11") (pinfunction "D_11") (pintype "bidirectional"))
      (node (ref "Q29") (pin "5") (pinfunction "D_5") (pintype "bidirectional"))
      (node (ref "Q29") (pin "6") (pinfunction "D_6") (pintype "bidirectional"))
      (node (ref "Q29") (pin "7") (pinfunction "D_7") (pintype "bidirectional"))
      (node (ref "Q29") (pin "8") (pinfunction "D_8") (pintype "bidirectional"))
      (node (ref "Q29") (pin "9") (pinfunction "D_9") (pintype "bidirectional"))
      (node (ref "Q31") (pin "2") (pinfunction "E_2") (pintype "passive"))
      (node (ref "Q32") (pin "10") (pinfunction "D_10") (pintype "bidirectional"))
      (node (ref "Q32") (pin "11") (pinfunction "D_11") (pintype "bidirectional"))
      (node (ref "Q32") (pin "5") (pinfunction "D_5") (pintype "bidirectional"))
      (node (ref "Q32") (pin "6") (pinfunction "D_6") (pintype "bidirectional"))
      (node (ref "Q32") (pin "7") (pinfunction "D_7") (pintype "bidirectional"))
      (node (ref "Q32") (pin "8") (pinfunction "D_8") (pintype "bidirectional"))
      (node (ref "Q32") (pin "9") (pinfunction "D_9") (pintype "bidirectional"))
      (node (ref "Q33") (pin "2") (pinfunction "E_2") (pintype "passive"))
      (node (ref "R6") (pin "P$2") (pinfunction "P$2_P$2") (pintype "passive"))
      (node (ref "R61") (pin "P$1") (pinfunction "P$1_P$1") (pintype "passive"))
      (node (ref "TP4") (pin "P1") (pinfunction "P$1_P1") (pintype "passive"))
      (node (ref "U2") (pin "3") (pinfunction "VIN_3") (pintype "power_in"))
      (node (ref "U3") (pin "9") (pinfunction "VIN_9") (pintype "power_in"))
    )
    (net (code "3") (name "+5V") (class "Default")
      (node (ref "C58") (pin "P$2") (pinfunction "P$2_P$2") (pintype "passive"))
      (node (ref "C60") (pin "P$2") (pinfunction "P$2_P$2") (pintype "passive"))
      (node (ref "J2") (pin "1") (pinfunction "VCC_1") (pintype "passive"))
      (node (ref "Q28") (pin "4") (pinfunction "G_4") (pintype "bidirectional"))
      (node (ref "Q32") (pin "1") (pinfunction "S_1") (pintype "bidirectional"))
      (node (ref "Q32") (pin "2") (pinfunction "S_2") (pintype "bidirectional"))
      (node (ref "Q32") (pin "3") (pinfunction "S_3") (pintype "bidirectional"))
      (node (ref "Q34") (pin "2") (pinfunction "E_2") (pintype "passive"))
      (node (ref "R48") (pin "2") (pinfunction "P$2_2") (pintype "passive"))
      (node (ref "R49") (pin "2") (pinfunction "P$2_2") (pintype "passive"))
      (node (ref "TP5") (pin "P1") (pinfunction "P$1_P1") (pintype "passive"))
      (node (ref "U5") (pin "4") (pinfunction "VDD_4") (pintype "power_in"))
    )
    (net (code "4") (name "+12V") (class "Default")
      (node (ref "C25") (pin "+") (pinfunction "+_+") (pintype "passive"))
      (node (ref "C65") (pin "P$2") (pinfunction "P$2_P$2") (pintype "passive"))
      (node (ref "C66") (pin "+") (pinfunction "+_+") (pintype "passive"))
      (node (ref "C68") (pin "P$2") (pinfunction "P$2_P$2") (pintype "passive"))
      (node (ref "C69") (pin "+") (pinfunction "+_+") (pintype "passive"))
      (node (ref "C71") (pin "P$2") (pinfunction "P$2_P$2") (pintype "passive"))
      (node (ref "C72") (pin "+") (pinfunction "+_+") (pintype "passive"))
      (node (ref "C74") (pin "P$2") (pinfunction "P$2_P$2") (pintype "passive"))
      (node (ref "C75") (pin "+") (pinfunction "+_+") (pintype "passive"))
      (node (ref "C80") (pin "+") (pinfunction "+_+") (pintype "passive"))
      (node (ref "R14") (pin "2") (pinfunction "P$2_2") (pintype "passive"))
      (node (ref "TP7") (pin "P1") (pinfunction "P$1_P1") (pintype "passive"))
      (node (ref "U10") (pin "5") (pinfunction "VM_5") (pintype "power_in"))
      (node (ref "U3") (pin "6") (pinfunction "VOUT_6") (pintype "output"))
      (node (ref "U7") (pin "5") (pinfunction "VM_5") (pintype "power_in"))
      (node (ref "U8") (pin "5") (pinfunction "VM_5") (pintype "power_in"))
      (node (ref "U9") (pin "5") (pinfunction "VM_5") (pintype "power_in"))
    )
    (net (code "5") (name "BT_EN") (class "Default")
      (node (ref "A5") (pin "6") (pinfunction "EN_6") (pintype "input"))
      (node (ref "U1") (pin "25") (pinfunction "PA16_25") (pintype "bidirectional"))
    )
    (net (code "6") (name "BT_RX") (class "Default")
      (node (ref "A5") (pin "3") (pinfunction "TXD_3") (pintype "output"))
      (node (ref "U1") (pin "22") (pinfunction "PA13_22") (pintype "bidirectional"))
    )
    (net (code "7") (name "BT_STATE") (class "Default")
      (node (ref "A5") (pin "1") (pinfunction "STATE_1") (pintype "output"))
      (node (ref "U1") (pin "16") (pinfunction "PA11_16") (pintype "bidirectional"))
    )
    (net (code "8") (name "BT_TX") (class "Default")
      (node (ref "A5") (pin "2") (pinfunction "RXD_2") (pintype "input"))
      (node (ref "U1") (pin "21") (pinfunction "PA12_21") (pintype "bidirectional"))
    )
    (net (code "9") (name "ENCODER_1A") (class "Default")
      (node (ref "A1") (pin "3") (pinfunction "OUTA_3") (pintype "output"))
      (node (ref "U1") (pin "30") (pinfunction "PA21_30") (pintype "bidirectional"))
    )
    (net (code "10") (name "ENCODER_1B") (class "Default")
      (node (ref "A1") (pin "4") (pinfunction "OUTB_4") (pintype "output"))
      (node (ref "U1") (pin "33") (pinfunction "PA24_33") (pintype "bidirectional"))
    )
    (net (code "11") (name "ENCODER_2A") (class "Default")
      (node (ref "A2") (pin "3") (pinfunction "OUTA_3") (pintype "output"))
      (node (ref "U1") (pin "27") (pinfunction "PA18_27") (pintype "bidirectional"))
    )
    (net (code "12") (name "ENCODER_2B") (class "Default")
      (node (ref "A2") (pin "4") (pinfunction "OUTB_4") (pintype "output"))
      (node (ref "U1") (pin "26") (pinfunction "PA17_26") (pintype "bidirectional"))
    )
    (net (code "13") (name "ENCODER_3A") (class "Default")
      (node (ref "A3") (pin "3") (pinfunction "OUTA_3") (pintype "output"))
      (node (ref "U1") (pin "29") (pinfunction "PA20_29") (pintype "bidirectional"))
    )
    (net (code "14") (name "ENCODER_3B") (class "Default")
      (node (ref "A3") (pin "4") (pinfunction "OUTB_4") (pintype "output"))
      (node (ref "U1") (pin "28") (pinfunction "PA19_28") (pintype "bidirectional"))
    )
    (net (code "15") (name "ENCODER_4A") (class "Default")
      (node (ref "A4") (pin "3") (pinfunction "OUTA_3") (pintype "output"))
      (node (ref "U1") (pin "38") (pinfunction "PB23_38") (pintype "bidirectional"))
    )
    (net (code "16") (name "ENCODER_4B") (class "Default")
      (node (ref "A4") (pin "4") (pinfunction "OUTB_4") (pintype "output"))
      (node (ref "U1") (pin "37") (pinfunction "PB22_37") (pintype "bidirectional"))
    )
    (net (code "17") (name "GND") (class "Default")
      (node (ref "A1") (pin "5") (pinfunction "GND_5") (pintype "passive"))
      (node (ref "A2") (pin "5") (pinfunction "GND_5") (pintype "passive"))
      (node (ref "A3") (pin "5") (pinfunction "GND_5") (pintype "passive"))
      (node (ref "A4") (pin "5") (pinfunction "GND_5") (pintype "passive"))
      (node (ref "A5") (pin "4") (pinfunction "GND_4") (pintype "passive"))
      (node (ref "C1") (pin "1") (pinfunction "P$1_1") (pintype "passive"))
      (node (ref "C11") (pin "1") (pinfunction "P$1_1") (pintype "passive"))
      (node (ref "C12") (pin "1") (pinfunction "P$1_1") (pintype "passive"))
      (node (ref "C13") (pin "1") (pinfunction "P$1_1") (pintype "passive"))
      (node (ref "C14") (pin "1") (pinfunction "P$1_1") (pintype "passive"))
      (node (ref "C15") (pin "1") (pinfunction "P$1_1") (pintype "passive"))
      (node (ref "C16") (pin "-") (pinfunction "-_-") (pintype "passive"))
      (node (ref "C18") (pin "-") (pinfunction "-_-") (pintype "passive"))
      (node (ref "C19") (pin "-") (pinfunction "-_-") (pintype "passive"))
      (node (ref "C2") (pin "1") (pinfunction "P$1_1") (pintype "passive"))
      (node (ref "C21") (pin "1") (pinfunction "P$1_1") (pintype "passive"))
      (node (ref "C22") (pin "-") (pinfunction "-_-") (pintype "passive"))
      (node (ref "C23") (pin "1") (pinfunction "P$1_1") (pintype "passive"))
      (node (ref "C24") (pin "1") (pinfunction "P$1_1") (pintype "passive"))
      (node (ref "C25") (pin "-") (pinfunction "-_-") (pintype "passive"))
      (node (ref "C26") (pin "P$1") (pinfunction "P$1_P$1") (pintype "passive"))
      (node (ref "C27") (pin "P$1") (pinfunction "P$1_P$1") (pintype "passive"))
      (node (ref "C28") (pin "P$1") (pinfunction "P$1_P$1") (pintype "passive"))
      (node (ref "C29") (pin "P$1") (pinfunction "P$1_P$1") (pintype "passive"))
      (node (ref "C3") (pin "1") (pinfunction "P$1_1") (pintype "passive"))
      (node (ref "C30") (pin "P$1") (pinfunction "P$1_P$1") (pintype "passive"))
      (node (ref "C31") (pin "P$1") (pinfunction "P$1_P$1") (pintype "passive"))
      (node (ref "C32") (pin "P$1") (pinfunction "P$1_P$1") (pintype "passive"))
      (node (ref "C33") (pin "1") (pinfunction "P$1_1") (pintype "passive"))
      (node (ref "C34") (pin "P$1") (pinfunction "P$1_P$1") (pintype "passive"))
      (node (ref "C35") (pin "P$1") (pinfunction "P$1_P$1") (pintype "passive"))
      (node (ref "C36") (pin "P$1") (pinfunction "P$1_P$1") (pintype "passive"))
      (node (ref "C37") (pin "P$1") (pinfunction "P$1_P$1") (pintype "passive"))
      (node (ref "C38") (pin "P$1") (pinfunction "P$1_P$1") (pintype "passive"))
      (node (ref "C39") (pin "P$1") (pinfunction "P$1_P$1") (pintype "passive"))
      (node (ref "C4") (pin "1") (pinfunction "P$1_1") (pintype "passive"))
      (node (ref "C40") (pin "1") (pinfunction "P$1_1") (pintype "passive"))
      (node (ref "C41") (pin "P$1") (pinfunction "P$1_P$1") (pintype "passive"))
      (node (ref "C42") (pin "1") (pinfunction "P$1_1") (pintype "passive"))
      (node (ref "C43") (pin "1") (pinfunction "P$1_1") (pintype "passive"))
      (node (ref "C44") (pin "1") (pinfunction "P$1_1") (pintype "passive"))
      (node (ref "C45") (pin "1") (pinfunction "P$1_1") (pintype "passive"))
      (node (ref "C46") (pin "1") (pinfunction "P$1_1") (pintype "passive"))
      (node (ref "C47") (pin "1") (pinfunction "P$1_1") (pintype "passive"))
      (node (ref "C48") (pin "1") (pinfunction "P$1_1") (pintype "passive"))
      (node (ref "C5") (pin "1") (pinfunction "P$1_1") (pintype "passive"))
      (node (ref "C52") (pin "1") (pinfunction "P$1_1") (pintype "passive"))
      (node (ref "C53") (pin "1") (pinfunction "P$1_1") (pintype "passive"))
      (node (ref "C54") (pin "1") (pinfunction "P$1_1") (pintype "passive"))
      (node (ref "C55") (pin "1") (pinfunction "P$1_1") (pintype "passive"))
      (node (ref "C56") (pin "1") (pinfunction "P$1_1") (pintype "passive"))
      (node (ref "C57") (pin "1") (pinfunction "P$1_1") (pintype "passive"))
      (node (ref "C58") (pin "P$1") (pinfunction "P$1_P$1") (pintype "passive"))
      (node (ref "C59") (pin "P$1") (pinfunction "P$1_P$1") (pintype "passive"))
      (node (ref "C6") (pin "1") (pinfunction "P$1_1") (pintype "passive"))
      (node (ref "C60") (pin "P$1") (pinfunction "P$1_P$1") (pintype "passive"))
      (node (ref "C61") (pin "P$1") (pinfunction "P$1_P$1") (pintype "passive"))
      (node (ref "C62") (pin "-") (pinfunction "-_-") (pintype "passive"))
      (node (ref "C63") (pin "1") (pinfunction "P$1_1") (pintype "passive"))
      (node (ref "C64") (pin "1") (pinfunction "P$1_1") (pintype "passive"))
      (node (ref "C65") (pin "P$1") (pinfunction "P$1_P$1") (pintype "passive"))
      (node (ref "C66") (pin "-") (pinfunction "-_-") (pintype "passive"))
      (node (ref "C67") (pin "P$1") (pinfunction "P$1_P$1") (pintype "passive"))
      (node (ref "C68") (pin "P$1") (pinfunction "P$1_P$1") (pintype "passive"))
      (node (ref "C69") (pin "-") (pinfunction "-_-") (pintype "passive"))
      (node (ref "C70") (pin "P$1") (pinfunction "P$1_P$1") (pintype "passive"))
      (node (ref "C71") (pin "P$1") (pinfunction "P$1_P$1") (pintype "passive"))
      (node (ref "C72") (pin "-") (pinfunction "-_-") (pintype "passive"))
      (node (ref "C73") (pin "P$1") (pinfunction "P$1_P$1") (pintype "passive"))
      (node (ref "C74") (pin "P$1") (pinfunction "P$1_P$1") (pintype "passive"))
      (node (ref "C75") (pin "-") (pinfunction "-_-") (pintype "passive"))
      (node (ref "C76") (pin "P$1") (pinfunction "P$1_P$1") (pintype "passive"))
      (node (ref "C78") (pin "1") (pinfunction "P$1_1") (pintype "passive"))
      (node (ref "C79") (pin "1") (pinfunction "P$1_1") (pintype "passive"))
      (node (ref "C8") (pin "1") (pinfunction "P$1_1") (pintype "passive"))
      (node (ref "C80") (pin "-") (pinfunction "-_-") (pintype "passive"))
      (node (ref "C9") (pin "1") (pinfunction "P$1_1") (pintype "passive"))
      (node (ref "J1") (pin "P2") (pinfunction "2_P2") (pintype "passive"))
      (node (ref "J1") (pin "P3") (pinfunction "3_P3") (pintype "passive"))
      (node (ref "J2") (pin "10") (pinfunction "GND_10") (pintype "passive"))
      (node (ref "J2") (pin "11") (pinfunction "GND_11") (pintype "passive"))
      (node (ref "J2") (pin "12") (pinfunction "GND_12") (pintype "passive"))
      (node (ref "J2") (pin "13") (pinfunction "GND_13") (pintype "passive"))
      (node (ref "J2") (pin "14") (pinfunction "GND_14") (pintype "passive"))
      (node (ref "J2") (pin "15") (pinfunction "GND_15") (pintype "passive"))
      (node (ref "J2") (pin "5") (pinfunction "GND_5") (pintype "passive"))
      (node (ref "J2") (pin "6") (pinfunction "GND_6") (pintype "passive"))
      (node (ref "J2") (pin "7") (pinfunction "GND_7") (pintype "passive"))
      (node (ref "J2") (pin "8") (pinfunction "GND_8") (pintype "passive"))
      (node (ref "J2") (pin "9") (pinfunction "GND_9") (pintype "passive"))
      (node (ref "J3") (pin "2") (pinfunction "2_2") (pintype "passive"))
      (node (ref "Q1") (pin "2") (pinfunction "E_2") (pintype "passive"))
      (node (ref "Q12") (pin "2") (pinfunction "E_2") (pintype "passive"))
      (node (ref "Q13") (pin "2") (pinfunction "E_2") (pintype "passive"))
      (node (ref "Q14") (pin "2") (pinfunction "E_2") (pintype "passive"))
      (node (ref "Q15") (pin "2") (pinfunction "E_2") (pintype "passive"))
      (node (ref "Q20") (pin "2") (pinfunction "E_2") (pintype "passive"))
      (node (ref "Q21") (pin "2") (pinfunction "E_2") (pintype "passive"))
      (node (ref "Q22") (pin "2") (pinfunction "E_2") (pintype "passive"))
      (node (ref "Q23") (pin "2") (pinfunction "E_2") (pintype "passive"))
      (node (ref "R11") (pin "1") (pinfunction "P$1_1") (pintype "passive"))
      (node (ref "R13") (pin "1") (pinfunction "P$1_1") (pintype "passive"))
      (node (ref "R21") (pin "1") (pinfunction "P$1_1") (pintype "passive"))
      (node (ref "R22") (pin "1") (pinfunction "P$1_1") (pintype "passive"))
      (node (ref "R23") (pin "1") (pinfunction "P$1_1") (pintype "passive"))
      (node (ref "R24") (pin "1") (pinfunction "P$1_1") (pintype "passive"))
      (node (ref "R30") (pin "P$1") (pinfunction "P$1_P$1") (pintype "passive"))
      (node (ref "R31") (pin "P$1") (pinfunction "P$1_P$1") (pintype "passive"))
      (node (ref "R32") (pin "P$1") (pinfunction "P$1_P$1") (pintype "passive"))
      (node (ref "R33") (pin "P$1") (pinfunction "P$1_P$1") (pintype "passive"))
      (node (ref "R38") (pin "P$1") (pinfunction "P$1_P$1") (pintype "passive"))
      (node (ref "R39") (pin "P$1") (pinfunction "P$1_P$1") (pintype "passive"))
      (node (ref "R4") (pin "P$1") (pinfunction "P$1_P$1") (pintype "passive"))
      (node (ref "R40") (pin "1") (pinfunction "P$1_1") (pintype "passive"))
      (node (ref "R41") (pin "P$1") (pinfunction "P$1_P$1") (pintype "passive"))
      (node (ref "R42") (pin "1") (pinfunction "P$1_1") (pintype "passive"))
      (node (ref "R45") (pin "1") (pinfunction "P$1_1") (pintype "passive"))
      (node (ref "R46") (pin "1") (pinfunction "P$1_1") (pintype "passive"))
      (node (ref "R47") (pin "1") (pinfunction "P$1_1") (pintype "passive"))
      (node (ref "R52") (pin "1") (pinfunction "P$1_1") (pintype "passive"))
      (node (ref "R53") (pin "1") (pinfunction "P$1_1") (pintype "passive"))
      (node (ref "R54") (pin "1") (pinfunction "P$1_1") (pintype "passive"))
      (node (ref "R58") (pin "P$1") (pinfunction "P$1_P$1") (pintype "passive"))
      (node (ref "R60") (pin "P$1") (pinfunction "P$1_P$1") (pintype "passive"))
      (node (ref "R64") (pin "P$1") (pinfunction "P$1_P$1") (pintype "passive"))
      (node (ref "R65") (pin "P$1") (pinfunction "P$1_P$1") (pintype "passive"))
      (node (ref "R66") (pin "P$1") (pinfunction "P$1_P$1") (pintype "passive"))
      (node (ref "R8") (pin "P$1") (pinfunction "P$1_P$1") (pintype "passive"))
      (node (ref "S1") (pin "1") (pinfunction "1_1") (pintype "passive"))
      (node (ref "S1") (pin "2") (pinfunction "1_2") (pintype "passive"))
      (node (ref "S1") (pin "5") (pinfunction "GND_5") (pintype "passive"))
      (node (ref "S1") (pin "6") (pinfunction "GND_6") (pintype "passive"))
      (node (ref "S2") (pin "4") (pinfunction "GND_4") (pintype "passive"))
      (node (ref "S2") (pin "5") (pinfunction "GND_5") (pintype "passive"))
      (node (ref "U1") (pin "18") (pinfunction "GND_18") (pintype "passive"))
      (node (ref "U1") (pin "35") (pinfunction "GND_35") (pintype "passive"))
      (node (ref "U1") (pin "42") (pinfunction "GND_42") (pintype "passive"))
      (node (ref "U1") (pin "49") (pinfunction "GND_49") (pintype "passive"))
      (node (ref "U1") (pin "5") (pinfunction "GNDANA_5") (pintype "passive"))
      (node (ref "U10") (pin "1") (pinfunction "GND_1") (pintype "passive"))
      (node (ref "U10") (pin "7") (pinfunction "PGND_7") (pintype "passive"))
      (node (ref "U10") (pin "9") (pinfunction "GND_9") (pintype "passive"))
      (node (ref "U11") (pin "25") (pinfunction "VSS_25") (pintype "passive"))
      (node (ref "U11") (pin "9") (pinfunction "VSS_9") (pintype "passive"))
      (node (ref "U12") (pin "17") (pinfunction "GND_17") (pintype "passive"))
      (node (ref "U12") (pin "6") (pinfunction "GND_6") (pintype "passive"))
      (node (ref "U2") (pin "4") (pinfunction "PGND_4") (pintype "passive"))
      (node (ref "U2") (pin "8") (pinfunction "SGND_8") (pintype "passive"))
      (node (ref "U2") (pin "9") (pinfunction "PGND_9") (pintype "passive"))
      (node (ref "U3") (pin "5") (pinfunction "GND_5") (pintype "passive"))
      (node (ref "U4") (pin "15") (pinfunction "GNDIO_15") (pintype "passive"))
      (node (ref "U4") (pin "16") (pinfunction "GNDIO_16") (pintype "passive"))
      (node (ref "U4") (pin "2") (pinfunction "GND_2") (pintype "passive"))
      (node (ref "U4") (pin "25") (pinfunction "GNDIO_25") (pintype "passive"))
      (node (ref "U5") (pin "2") (pinfunction "VSS_2") (pintype "passive"))
      (node (ref "U6") (pin "2") (pinfunction "GND_2") (pintype "passive"))
      (node (ref "U6") (pin "3") (pinfunction "GND_3") (pintype "passive"))
      (node (ref "U6") (pin "5") (pinfunction "GND_5") (pintype "passive"))
      (node (ref "U7") (pin "1") (pinfunction "GND_1") (pintype "passive"))
      (node (ref "U7") (pin "7") (pinfunction "PGND_7") (pintype "passive"))
      (node (ref "U7") (pin "9") (pinfunction "GND_9") (pintype "passive"))
      (node (ref "U8") (pin "1") (pinfunction "GND_1") (pintype "passive"))
      (node (ref "U8") (pin "7") (pinfunction "PGND_7") (pintype "passive"))
      (node (ref "U8") (pin "9") (pinfunction "GND_9") (pintype "passive"))
      (node (ref "U9") (pin "1") (pinfunction "GND_1") (pintype "passive"))
      (node (ref "U9") (pin "7") (pinfunction "PGND_7") (pintype "passive"))
      (node (ref "U9") (pin "9") (pinfunction "GND_9") (pintype "passive"))
    )
    (net (code "18") (name "IMU_INT") (class "Default")
      (node (ref "U1") (pin "19") (pinfunction "PB10_19") (pintype "bidirectional"))
      (node (ref "U4") (pin "14") (pinfunction "INT_14") (pintype "output"))
    )
    (net (code "19") (name "IR1") (class "Default")
      (node (ref "Q12") (pin "1") (pinfunction "B_1") (pintype "passive"))
      (node (ref "TP8") (pin "P1") (pinfunction "P$1_P1") (pintype "passive"))
      (node (ref "U11") (pin "10") (pinfunction "P1_0_10") (pintype "bidirectional"))
    )
    (net (code "20") (name "IR2") (class "Default")
      (node (ref "Q13") (pin "1") (pinfunction "B_1") (pintype "passive"))
      (node (ref "U11") (pin "15") (pinfunction "P1_5_15") (pintype "bidirectional"))
    )
    (net (code "21") (name "IR3") (class "Default")
      (node (ref "Q14") (pin "1") (pinfunction "B_1") (pintype "passive"))
      (node (ref "U11") (pin "14") (pinfunction "P1_4_14") (pintype "bidirectional"))
    )
    (net (code "22") (name "IR4") (class "Default")
      (node (ref "Q15") (pin "1") (pinfunction "B_1") (pintype "passive"))
      (node (ref "U11") (pin "13") (pinfunction "P1_3_13") (pintype "bidirectional"))
    )
    (net (code "23") (name "IR5") (class "Default")
      (node (ref "Q20") (pin "1") (pinfunction "B_1") (pintype "passive"))
      (node (ref "U11") (pin "11") (pinfunction "P1_1_11") (pintype "bidirectional"))
    )
    (net (code "24") (name "IR6") (class "Default")
      (node (ref "Q21") (pin "1") (pinfunction "B_1") (pintype "passive"))
      (node (ref "U11") (pin "12") (pinfunction "P1_2_12") (pintype "bidirectional"))
    )
    (net (code "25") (name "IR7") (class "Default")
      (node (ref "Q22") (pin "1") (pinfunction "B_1") (pintype "passive"))
      (node (ref "U11") (pin "16") (pinfunction "P1_6_16") (pintype "bidirectional"))
    )
    (net (code "26") (name "IR8") (class "Default")
      (node (ref "Q23") (pin "1") (pinfunction "B_1") (pintype "passive"))
      (node (ref "U11") (pin "17") (pinfunction "P1_7_17") (pintype "bidirectional"))
    )
    (net (code "27") (name "LED0") (class "Default")
      (node (ref "R16") (pin "1") (pinfunction "P$1_1") (pintype "passive"))
      (node (ref "U11") (pin "1") (pinfunction "P0_0_1") (pintype "bidirectional"))
    )
    (net (code "28") (name "LED1") (class "Default")
      (node (ref "R17") (pin "1") (pinfunction "P$1_1") (pintype "passive"))
      (node (ref "U11") (pin "2") (pinfunction "P0_1_2") (pintype "bidirectional"))
    )
    (net (code "29") (name "LED2") (class "Default")
      (node (ref "R18") (pin "1") (pinfunction "P$1_1") (pintype "passive"))
      (node (ref "U11") (pin "4") (pinfunction "P0_3_4") (pintype "bidirectional"))
    )
    (net (code "30") (name "LED3") (class "Default")
      (node (ref "R19") (pin "1") (pinfunction "P$1_1") (pintype "passive"))
      (node (ref "U11") (pin "5") (pinfunction "P0_4_5") (pintype "bidirectional"))
    )
    (net (code "31") (name "LED4") (class "Default")
      (node (ref "R20") (pin "1") (pinfunction "P$1_1") (pintype "passive"))
      (node (ref "U11") (pin "3") (pinfunction "P0_2_3") (pintype "bidirectional"))
    )
    (net (code "32") (name "MOTOR_1A") (class "Default")
      (node (ref "U12") (pin "4") (pinfunction "P3_4") (pintype "bidirectional"))
      (node (ref "U7") (pin "3") (pinfunction "IN1_3") (pintype "input"))
    )
    (net (code "33") (name "MOTOR_1B") (class "Default")
      (node (ref "U12") (pin "5") (pinfunction "P4_5") (pintype "bidirectional"))
      (node (ref "U7") (pin "2") (pinfunction "IN2_2") (pintype "input"))
    )
    (net (code "34") (name "MOTOR_2A") (class "Default")
      (node (ref "U12") (pin "2") (pinfunction "P1_2") (pintype "bidirectional"))
      (node (ref "U8") (pin "3") (pinfunction "IN1_3") (pintype "input"))
    )
    (net (code "35") (name "MOTOR_2B") (class "Default")
      (node (ref "U12") (pin "3") (pinfunction "P2_3") (pintype "bidirectional"))
      (node (ref "U8") (pin "2") (pinfunction "IN2_2") (pintype "input"))
    )
    (net (code "36") (name "MOTOR_3A") (class "Default")
      (node (ref "U12") (pin "9") (pinfunction "P7_9") (pintype "bidirectional"))
      (node (ref "U9") (pin "3") (pinfunction "IN1_3") (pintype "input"))
    )
    (net (code "37") (name "MOTOR_3B") (class "Default")
      (node (ref "U12") (pin "10") (pinfunction "P8_10") (pintype "bidirectional"))
      (node (ref "U9") (pin "2") (pinfunction "IN2_2") (pintype "input"))
    )
    (net (code "38") (name "MOTOR_4A") (class "Default")
      (node (ref "U10") (pin "3") (pinfunction "IN1_3") (pintype "input"))
      (node (ref "U12") (pin "7") (pinfunction "P5_7") (pintype "bidirectional"))
    )
    (net (code "39") (name "MOTOR_4B") (class "Default")
      (node (ref "U10") (pin "2") (pinfunction "IN2_2") (pintype "input"))
      (node (ref "U12") (pin "8") (pinfunction "P6_8") (pintype "bidirectional"))
    )
    (net (code "40") (name "Net-(A1-MA)") (class "Default")
      (node (ref "A1") (pin "1") (pinfunction "MA_1") (pintype "input"))
      (node (ref "U7") (pin "6") (pinfunction "OUT1_6") (pintype "output"))
    )
    (net (code "41") (name "Net-(A1-MB)") (class "Default")
      (node (ref "A1") (pin "6") (pinfunction "MB_6") (pintype "input"))
      (node (ref "U7") (pin "8") (pinfunction "OUT2_8") (pintype "output"))
    )
    (net (code "42") (name "Net-(A2-MA)") (class "Default")
      (node (ref "A2") (pin "1") (pinfunction "MA_1") (pintype "input"))
      (node (ref "U8") (pin "6") (pinfunction "OUT1_6") (pintype "output"))
    )
    (net (code "43") (name "Net-(A2-MB)") (class "Default")
      (node (ref "A2") (pin "6") (pinfunction "MB_6") (pintype "input"))
      (node (ref "U8") (pin "8") (pinfunction "OUT2_8") (pintype "output"))
    )
    (net (code "44") (name "Net-(A3-MA)") (class "Default")
      (node (ref "A3") (pin "1") (pinfunction "MA_1") (pintype "input"))
      (node (ref "U9") (pin "6") (pinfunction "OUT1_6") (pintype "output"))
    )
    (net (code "45") (name "Net-(A3-MB)") (class "Default")
      (node (ref "A3") (pin "6") (pinfunction "MB_6") (pintype "input"))
      (node (ref "U9") (pin "8") (pinfunction "OUT2_8") (pintype "output"))
    )
    (net (code "46") (name "Net-(A4-MA)") (class "Default")
      (node (ref "A4") (pin "1") (pinfunction "MA_1") (pintype "input"))
      (node (ref "U10") (pin "6") (pinfunction "OUT1_6") (pintype "output"))
    )
    (net (code "47") (name "Net-(A4-MB)") (class "Default")
      (node (ref "A4") (pin "6") (pinfunction "MB_6") (pintype "input"))
      (node (ref "U10") (pin "8") (pinfunction "OUT2_8") (pintype "output"))
    )
    (net (code "48") (name "Net-(C1-P$2)") (class "Default")
      (node (ref "C1") (pin "2") (pinfunction "P$2_2") (pintype "passive"))
      (node (ref "C2") (pin "2") (pinfunction "P$2_2") (pintype "passive"))
      (node (ref "FB1") (pin "1") (pinfunction "P$1_1") (pintype "passive"))
      (node (ref "U1") (pin "6") (pinfunction "VDDANA_6") (pintype "power_in"))
    )
    (net (code "49") (name "Net-(C5-P$2)") (class "Default")
      (node (ref "C5") (pin "2") (pinfunction "P$2_2") (pintype "passive"))
      (node (ref "U1") (pin "43") (pinfunction "VDDCORE_43") (pintype "power_in"))
    )
    (net (code "50") (name "Net-(C20-P$1)") (class "Default")
      (node (ref "C20") (pin "1") (pinfunction "P$1_1") (pintype "passive"))
      (node (ref "U3") (pin "10") (pinfunction "BOOT_10") (pintype "input"))
    )
    (net (code "51") (name "Net-(C20-P$2)") (class "Default")
      (node (ref "C20") (pin "2") (pinfunction "P$2_2") (pintype "passive"))
      (node (ref "L1") (pin "1") (pinfunction "P$1_1") (pintype "passive"))
      (node (ref "R9") (pin "2") (pinfunction "P$2_2") (pintype "passive"))
      (node (ref "U3") (pin "11") (pinfunction "SW_11") (pintype "output"))
      (node (ref "U3") (pin "12") (pinfunction "SW_12") (pintype "output"))
      (node (ref "U3") (pin "13") (pinfunction "SW_13") (pintype "output"))
    )
    (net (code "52") (name "Net-(C21-P$2)") (class "Default")
      (node (ref "C21") (pin "2") (pinfunction "P$2_2") (pintype "passive"))
      (node (ref "U3") (pin "2") (pinfunction "VCC_2") (pintype "power_in"))
    )
    (net (code "53") (name "Net-(C23-P$2)") (class "Default")
      (node (ref "C23") (pin "2") (pinfunction "P$2_2") (pintype "passive"))
      (node (ref "R12") (pin "2") (pinfunction "P$2_2") (pintype "passive"))
      (node (ref "U3") (pin "4") (pinfunction "COMP_4") (pintype "bidirectional"))
    )
    (net (code "54") (name "Net-(C24-P$2)") (class "Default")
      (node (ref "C24") (pin "2") (pinfunction "P$2_2") (pintype "passive"))
      (node (ref "R12") (pin "1") (pinfunction "P$1_1") (pintype "passive"))
    )
    (net (code "55") (name "Net-(C55-P$2)") (class "Default")
      (node (ref "C55") (pin "2") (pinfunction "P$2_2") (pintype "passive"))
      (node (ref "U4") (pin "9") (pinfunction "CAP_9") (pintype "passive"))
    )
    (net (code "56") (name "Net-(C56-P$2)") (class "Default")
      (node (ref "C56") (pin "2") (pinfunction "P$2_2") (pintype "passive"))
      (node (ref "U4") (pin "26") (pinfunction "XOUT32_26") (pintype "output"))
      (node (ref "XTAL3") (pin "1") (pinfunction "P$1_1") (pintype "passive"))
    )
    (net (code "57") (name "Net-(C57-P$2)") (class "Default")
      (node (ref "C57") (pin "2") (pinfunction "P$2_2") (pintype "passive"))
      (node (ref "U4") (pin "27") (pinfunction "XIN32_27") (pintype "input"))
      (node (ref "XTAL3") (pin "2") (pinfunction "P$2_2") (pintype "passive"))
    )
    (net (code "58") (name "Net-(C61-PadP$2)") (class "Default")
      (node (ref "C61") (pin "P$2") (pinfunction "P$2_P$2") (pintype "passive"))
      (node (ref "J3") (pin "1") (pinfunction "1_1") (pintype "passive"))
      (node (ref "R61") (pin "P$2") (pinfunction "P$2_P$2") (pintype "passive"))
      (node (ref "R62") (pin "P$2") (pinfunction "P$2_P$2") (pintype "passive"))
    )
    (net (code "59") (name "Net-(C63-P$2)") (class "Default")
      (node (ref "C63") (pin "2") (pinfunction "P$2_2") (pintype "passive"))
      (node (ref "C8") (pin "2") (pinfunction "P$2_2") (pintype "passive"))
      (node (ref "C9") (pin "2") (pinfunction "P$2_2") (pintype "passive"))
      (node (ref "FB2") (pin "1") (pinfunction "P$1_1") (pintype "passive"))
      (node (ref "U6") (pin "1") (pinfunction "OUT_1") (pintype "power_in"))
    )
    (net (code "60") (name "Net-(D1-IN)") (class "Default")
      (node (ref "D1") (pin "1") (pinfunction "IN_1") (pintype "passive"))
      (node (ref "R15") (pin "P$1") (pinfunction "P$1_P$1") (pintype "passive"))
    )
    (net (code "61") (name "Net-(D1-OUT)") (class "Default")
      (node (ref "D1") (pin "2") (pinfunction "OUT_2") (pintype "passive"))
      (node (ref "Q1") (pin "3") (pinfunction "C_3") (pintype "passive"))
    )
    (net (code "62") (name "Net-(D2-OUT)") (class "Default")
      (node (ref "D2") (pin "2") (pinfunction "OUT_2") (pintype "passive"))
      (node (ref "R16") (pin "2") (pinfunction "P$2_2") (pintype "passive"))
    )
    (net (code "63") (name "Net-(D3-OUT)") (class "Default")
      (node (ref "D3") (pin "2") (pinfunction "OUT_2") (pintype "passive"))
      (node (ref "R17") (pin "2") (pinfunction "P$2_2") (pintype "passive"))
    )
    (net (code "64") (name "Net-(D4-OUT)") (class "Default")
      (node (ref "D4") (pin "2") (pinfunction "OUT_2") (pintype "passive"))
      (node (ref "R18") (pin "2") (pinfunction "P$2_2") (pintype "passive"))
    )
    (net (code "65") (name "Net-(D5-OUT)") (class "Default")
      (node (ref "D5") (pin "2") (pinfunction "OUT_2") (pintype "passive"))
      (node (ref "R19") (pin "2") (pinfunction "P$2_2") (pintype "passive"))
    )
    (net (code "66") (name "Net-(D6-OUT)") (class "Default")
      (node (ref "D6") (pin "2") (pinfunction "OUT_2") (pintype "passive"))
      (node (ref "R20") (pin "2") (pinfunction "P$2_2") (pintype "passive"))
    )
    (net (code "67") (name "Net-(D12-IN)") (class "Default")
      (node (ref "D12") (pin "+") (pinfunction "IN_+") (pintype "passive"))
      (node (ref "R26") (pin "P$2") (pinfunction "P$2_P$2") (pintype "passive"))
    )
    (net (code "68") (name "Net-(D12-OUT)") (class "Default")
      (node (ref "D12") (pin "-") (pinfunction "OUT_-") (pintype "passive"))
      (node (ref "Q12") (pin "3") (pinfunction "C_3") (pintype "passive"))
    )
    (net (code "69") (name "Net-(D13-IN)") (class "Default")
      (node (ref "D13") (pin "+") (pinfunction "IN_+") (pintype "passive"))
      (node (ref "R27") (pin "P$2") (pinfunction "P$2_P$2") (pintype "passive"))
    )
    (net (code "70") (name "Net-(D13-OUT)") (class "Default")
      (node (ref "D13") (pin "-") (pinfunction "OUT_-") (pintype "passive"))
      (node (ref "Q13") (pin "3") (pinfunction "C_3") (pintype "passive"))
    )
    (net (code "71") (name "Net-(D14-IN)") (class "Default")
      (node (ref "D14") (pin "+") (pinfunction "IN_+") (pintype "passive"))
      (node (ref "R28") (pin "P$2") (pinfunction "P$2_P$2") (pintype "passive"))
    )
    (net (code "72") (name "Net-(D14-OUT)") (class "Default")
      (node (ref "D14") (pin "-") (pinfunction "OUT_-") (pintype "passive"))
      (node (ref "Q14") (pin "3") (pinfunction "C_3") (pintype "passive"))
    )
    (net (code "73") (name "Net-(D15-IN)") (class "Default")
      (node (ref "D15") (pin "+") (pinfunction "IN_+") (pintype "passive"))
      (node (ref "R29") (pin "P$2") (pinfunction "P$2_P$2") (pintype "passive"))
    )
    (net (code "74") (name "Net-(D15-OUT)") (class "Default")
      (node (ref "D15") (pin "-") (pinfunction "OUT_-") (pintype "passive"))
      (node (ref "Q15") (pin "3") (pinfunction "C_3") (pintype "passive"))
    )
    (net (code "75") (name "Net-(D16-IN)") (class "Default")
      (node (ref "D16") (pin "+") (pinfunction "IN_+") (pintype "passive"))
      (node (ref "R34") (pin "P$2") (pinfunction "P$2_P$2") (pintype "passive"))
    )
    (net (code "76") (name "Net-(D16-OUT)") (class "Default")
      (node (ref "D16") (pin "-") (pinfunction "OUT_-") (pintype "passive"))
      (node (ref "Q20") (pin "3") (pinfunction "C_3") (pintype "passive"))
    )
    (net (code "77") (name "Net-(D17-IN)") (class "Default")
      (node (ref "D17") (pin "+") (pinfunction "IN_+") (pintype "passive"))
      (node (ref "R35") (pin "P$2") (pinfunction "P$2_P$2") (pintype "passive"))
    )
    (net (code "78") (name "Net-(D17-OUT)") (class "Default")
      (node (ref "D17") (pin "-") (pinfunction "OUT_-") (pintype "passive"))
      (node (ref "Q21") (pin "3") (pinfunction "C_3") (pintype "passive"))
    )
    (net (code "79") (name "Net-(D18-IN)") (class "Default")
      (node (ref "D18") (pin "+") (pinfunction "IN_+") (pintype "passive"))
      (node (ref "R36") (pin "P$2") (pinfunction "P$2_P$2") (pintype "passive"))
    )
    (net (code "80") (name "Net-(D18-OUT)") (class "Default")
      (node (ref "D18") (pin "-") (pinfunction "OUT_-") (pintype "passive"))
      (node (ref "Q22") (pin "3") (pinfunction "C_3") (pintype "passive"))
    )
    (net (code "81") (name "Net-(D19-IN)") (class "Default")
      (node (ref "D19") (pin "+") (pinfunction "IN_+") (pintype "passive"))
      (node (ref "R37") (pin "P$2") (pinfunction "P$2_P$2") (pintype "passive"))
    )
    (net (code "82") (name "Net-(D19-OUT)") (class "Default")
      (node (ref "D19") (pin "-") (pinfunction "OUT_-") (pintype "passive"))
      (node (ref "Q23") (pin "3") (pinfunction "C_3") (pintype "passive"))
    )
    (net (code "83") (name "Net-(J2-D+)") (class "Default")
      (node (ref "J2") (pin "3") (pinfunction "D+_3") (pintype "passive"))
      (node (ref "R53") (pin "2") (pinfunction "P$2_2") (pintype "passive"))
    )
    (net (code "84") (name "Net-(J2-D-)") (class "Default")
      (node (ref "J2") (pin "2") (pinfunction "D-_2") (pintype "passive"))
      (node (ref "R54") (pin "2") (pinfunction "P$2_2") (pintype "passive"))
    )
    (net (code "85") (name "Net-(J2-ID)") (class "Default")
      (node (ref "J2") (pin "4") (pinfunction "ID_4") (pintype "passive"))
      (node (ref "R52") (pin "2") (pinfunction "P$2_2") (pintype "passive"))
    )
    (net (code "86") (name "Net-(L2-P$1)") (class "Default")
      (node (ref "L2") (pin "1") (pinfunction "P$1_1") (pintype "passive"))
      (node (ref "U2") (pin "6") (pinfunction "LX_6") (pintype "output"))
    )
    (net (code "87") (name "Net-(Q1-B)") (class "Default")
      (node (ref "Q1") (pin "1") (pinfunction "B_1") (pintype "passive"))
      (node (ref "U2") (pin "2") (pinfunction "PG_2") (pintype "output"))
    )
    (net (code "88") (name "Net-(Q29-G)") (class "Default")
      (node (ref "Q29") (pin "4") (pinfunction "G_4") (pintype "bidirectional"))
      (node (ref "Q31") (pin "3") (pinfunction "C_3") (pintype "passive"))
      (node (ref "R57") (pin "1") (pinfunction "P$1_1") (pintype "passive"))
    )
    (net (code "89") (name "Net-(Q30-B)") (class "Default")
      (node (ref "Q30") (pin "1") (pinfunction "B_1") (pintype "passive"))
      (node (ref "R56") (pin "2") (pinfunction "P$2_2") (pintype "passive"))
    )
    (net (code "90") (name "Net-(Q30-C)") (class "Default")
      (node (ref "Q30") (pin "3") (pinfunction "C_3") (pintype "passive"))
      (node (ref "R55") (pin "1") (pinfunction "P$1_1") (pintype "passive"))
    )
    (net (code "91") (name "Net-(Q30-E)") (class "Default")
      (node (ref "Q28") (pin "10") (pinfunction "D_10") (pintype "bidirectional"))
      (node (ref "Q28") (pin "11") (pinfunction "D_11") (pintype "bidirectional"))
      (node (ref "Q28") (pin "5") (pinfunction "D_5") (pintype "bidirectional"))
      (node (ref "Q28") (pin "6") (pinfunction "D_6") (pintype "bidirectional"))
      (node (ref "Q28") (pin "7") (pinfunction "D_7") (pintype "bidirectional"))
      (node (ref "Q28") (pin "8") (pinfunction "D_8") (pintype "bidirectional"))
      (node (ref "Q28") (pin "9") (pinfunction "D_9") (pintype "bidirectional"))
      (node (ref "Q29") (pin "1") (pinfunction "S_1") (pintype "bidirectional"))
      (node (ref "Q29") (pin "2") (pinfunction "S_2") (pintype "bidirectional"))
      (node (ref "Q29") (pin "3") (pinfunction "S_3") (pintype "bidirectional"))
      (node (ref "Q30") (pin "2") (pinfunction "E_2") (pintype "passive"))
      (node (ref "R55") (pin "2") (pinfunction "P$2_2") (pintype "passive"))
      (node (ref "R57") (pin "2") (pinfunction "P$2_2") (pintype "passive"))
    )
    (net (code "92") (name "Net-(Q31-B)") (class "Default")
      (node (ref "Q31") (pin "1") (pinfunction "B_1") (pintype "passive"))
      (node (ref "R56") (pin "1") (pinfunction "P$1_1") (pintype "passive"))
    )
    (net (code "93") (name "Net-(Q32-G)") (class "Default")
      (node (ref "Q32") (pin "4") (pinfunction "G_4") (pintype "bidirectional"))
      (node (ref "Q33") (pin "3") (pinfunction "C_3") (pintype "passive"))
      (node (ref "R58") (pin "P$2") (pinfunction "P$2_P$2") (pintype "passive"))
    )
    (net (code "94") (name "Net-(Q33-B)") (class "Default")
      (node (ref "Q33") (pin "1") (pinfunction "B_1") (pintype "passive"))
      (node (ref "R59") (pin "P$2") (pinfunction "P$2_P$2") (pintype "passive"))
    )
    (net (code "95") (name "Net-(Q34-B)") (class "Default")
      (node (ref "Q34") (pin "1") (pinfunction "B_1") (pintype "passive"))
      (node (ref "R59") (pin "P$1") (pinfunction "P$1_P$1") (pintype "passive"))
    )
    (net (code "96") (name "Net-(Q34-C)") (class "Default")
      (node (ref "Q34") (pin "3") (pinfunction "C_3") (pintype "passive"))
      (node (ref "R60") (pin "P$2") (pinfunction "P$2_P$2") (pintype "passive"))
    )
    (net (code "97") (name "Net-(R2-PadP$1)") (class "Default")
      (node (ref "R2") (pin "P$1") (pinfunction "P$1_P$1") (pintype "passive"))
      (node (ref "S1") (pin "3") (pinfunction "2_3") (pintype "passive"))
      (node (ref "S1") (pin "4") (pinfunction "2_4") (pintype "passive"))
    )
    (net (code "98") (name "Net-(R3-P$1)") (class "Default")
      (node (ref "R3") (pin "1") (pinfunction "P$1_1") (pintype "passive"))
      (node (ref "U11") (pin "24") (pinfunction "~{RESET}_24") (pintype "input"))
    )
    (net (code "99") (name "Net-(R9-P$1)") (class "Default")
      (node (ref "R9") (pin "1") (pinfunction "P$1_1") (pintype "passive"))
      (node (ref "U3") (pin "1") (pinfunction "FSW_1") (pintype "input"))
    )
    (net (code "100") (name "Net-(R10-P$1)") (class "Default")
      (node (ref "R10") (pin "1") (pinfunction "P$1_1") (pintype "passive"))
      (node (ref "U3") (pin "7") (pinfunction "EN_7") (pintype "input"))
    )
    (net (code "101") (name "Net-(R11-P$2)") (class "Default")
      (node (ref "R11") (pin "2") (pinfunction "P$2_2") (pintype "passive"))
      (node (ref "U3") (pin "8") (pinfunction "ILIM_8") (pintype "passive"))
    )
    (net (code "102") (name "Net-(R13-P$2)") (class "Default")
      (node (ref "R13") (pin "2") (pinfunction "P$2_2") (pintype "passive"))
      (node (ref "R14") (pin "1") (pinfunction "P$1_1") (pintype "passive"))
      (node (ref "U3") (pin "3") (pinfunction "FB_3") (pintype "input"))
    )
    (net (code "103") (name "Net-(R21-P$2)") (class "Default")
      (node (ref "R21") (pin "2") (pinfunction "P$2_2") (pintype "passive"))
      (node (ref "U11") (pin "18") (pinfunction "ADDR_18") (pintype "input"))
    )
    (net (code "104") (name "Net-(R22-P$2)") (class "Default")
      (node (ref "R22") (pin "2") (pinfunction "P$2_2") (pintype "passive"))
      (node (ref "U12") (pin "1") (pinfunction "AD2_1") (pintype "input"))
    )
    (net (code "105") (name "Net-(R23-P$2)") (class "Default")
      (node (ref "R23") (pin "2") (pinfunction "P$2_2") (pintype "passive"))
      (node (ref "U12") (pin "16") (pinfunction "AD1_16") (pintype "input"))
    )
    (net (code "106") (name "Net-(R24-P$2)") (class "Default")
      (node (ref "R24") (pin "2") (pinfunction "P$2_2") (pintype "passive"))
      (node (ref "U12") (pin "15") (pinfunction "AD0_15") (pintype "input"))
    )
    (net (code "107") (name "Net-(R42-P$2)") (class "Default")
      (node (ref "R42") (pin "2") (pinfunction "P$2_2") (pintype "passive"))
      (node (ref "U4") (pin "5") (pinfunction "PS1_5") (pintype "input"))
    )
    (net (code "108") (name "Net-(R43-P$1)") (class "Default")
      (node (ref "R43") (pin "1") (pinfunction "P$1_1") (pintype "passive"))
      (node (ref "U4") (pin "11") (pinfunction "~{RESET}_11") (pintype "input"))
    )
    (net (code "109") (name "Net-(R44-P$1)") (class "Default")
      (node (ref "R44") (pin "1") (pinfunction "P$1_1") (pintype "passive"))
      (node (ref "U4") (pin "4") (pinfunction "~{BOOTLOAD_PIN}_4") (pintype "input"))
    )
    (net (code "110") (name "Net-(R45-P$2)") (class "Default")
      (node (ref "R45") (pin "2") (pinfunction "P$2_2") (pintype "passive"))
      (node (ref "U4") (pin "6") (pinfunction "PS0_6") (pintype "input"))
    )
    (net (code "111") (name "Net-(R46-P$2)") (class "Default")
      (node (ref "R46") (pin "2") (pinfunction "P$2_2") (pintype "passive"))
      (node (ref "U4") (pin "17") (pinfunction "COM3_17") (pintype "output"))
    )
    (net (code "112") (name "Net-(R47-P$2)") (class "Default")
      (node (ref "R47") (pin "2") (pinfunction "P$2_2") (pintype "passive"))
      (node (ref "U4") (pin "18") (pinfunction "COM2_18") (pintype "bidirectional"))
    )
    (net (code "113") (name "Net-(R48-P$1)") (class "Default")
      (node (ref "R48") (pin "1") (pinfunction "P$1_1") (pintype "passive"))
      (node (ref "U5") (pin "1") (pinfunction "CE_1") (pintype "input"))
    )
    (net (code "114") (name "Net-(R49-P$1)") (class "Default")
      (node (ref "R49") (pin "1") (pinfunction "P$1_1") (pintype "passive"))
      (node (ref "U5") (pin "5") (pinfunction "PROG_5") (pintype "input"))
    )
    (net (code "115") (name "Net-(R63-P$1)") (class "Default")
      (node (ref "R63") (pin "1") (pinfunction "P$1_1") (pintype "passive"))
      (node (ref "U6") (pin "4") (pinfunction "~{SHDN}_4") (pintype "input"))
    )
    (net (code "116") (name "Net-(S2-2)") (class "Default")
      (node (ref "S2") (pin "3") (pinfunction "2_3") (pintype "passive"))
      (node (ref "U2") (pin "7") (pinfunction "EN_7") (pintype "input"))
    )
    (net (code "117") (name "Net-(S2-COMMON)") (class "Default")
      (node (ref "R6") (pin "P$1") (pinfunction "P$1_P$1") (pintype "passive"))
      (node (ref "S2") (pin "2") (pinfunction "COMMON_2") (pintype "passive"))
    )
    (net (code "118") (name "Net-(TP3-P$1)") (class "Default")
      (node (ref "C59") (pin "P$2") (pinfunction "P$2_P$2") (pintype "passive"))
      (node (ref "Q28") (pin "1") (pinfunction "S_1") (pintype "bidirectional"))
      (node (ref "Q28") (pin "2") (pinfunction "S_2") (pintype "bidirectional"))
      (node (ref "Q28") (pin "3") (pinfunction "S_3") (pintype "bidirectional"))
      (node (ref "R62") (pin "P$1") (pinfunction "P$1_P$1") (pintype "passive"))
      (node (ref "TP3") (pin "P1") (pinfunction "P$1_P1") (pintype "passive"))
      (node (ref "U5") (pin "3") (pinfunction "VBAT_3") (pintype "output"))
    )
    (net (code "119") (name "Net-(U2-FB)") (class "Default")
      (node (ref "C17") (pin "P$1") (pinfunction "P$1_P$1") (pintype "passive"))
      (node (ref "R7") (pin "P$1") (pinfunction "P$1_P$1") (pintype "passive"))
      (node (ref "R8") (pin "P$2") (pinfunction "P$2_P$2") (pintype "passive"))
      (node (ref "U2") (pin "1") (pinfunction "FB_1") (pintype "input"))
    )
    (net (code "120") (name "Net-(U7-ILIM)") (class "Default")
      (node (ref "R4") (pin "P$2") (pinfunction "P$2_P$2") (pintype "passive"))
      (node (ref "U7") (pin "4") (pinfunction "ILIM_4") (pintype "output"))
    )
    (net (code "121") (name "Net-(U8-ILIM)") (class "Default")
      (node (ref "R64") (pin "P$2") (pinfunction "P$2_P$2") (pintype "passive"))
      (node (ref "U8") (pin "4") (pinfunction "ILIM_4") (pintype "output"))
    )
    (net (code "122") (name "Net-(U9-ILIM)") (class "Default")
      (node (ref "R65") (pin "P$2") (pinfunction "P$2_P$2") (pintype "passive"))
      (node (ref "U9") (pin "4") (pinfunction "ILIM_4") (pintype "output"))
    )
    (net (code "123") (name "Net-(U10-ILIM)") (class "Default")
      (node (ref "R66") (pin "P$2") (pinfunction "P$2_P$2") (pintype "passive"))
      (node (ref "U10") (pin "4") (pinfunction "ILIM_4") (pintype "output"))
    )
    (net (code "124") (name "PHOTO1") (class "Default")
      (node (ref "Q16") (pin "E") (pinfunction "E_E") (pintype "passive"))
      (node (ref "R30") (pin "P$2") (pinfunction "P$2_P$2") (pintype "passive"))
      (node (ref "TP9") (pin "P1") (pinfunction "P$1_P1") (pintype "passive"))
      (node (ref "U1") (pin "9") (pinfunction "PA04_9") (pintype "bidirectional"))
    )
    (net (code "125") (name "PHOTO2") (class "Default")
      (node (ref "Q17") (pin "E") (pinfunction "E_E") (pintype "passive"))
      (node (ref "R31") (pin "P$2") (pinfunction "P$2_P$2") (pintype "passive"))
      (node (ref "U1") (pin "10") (pinfunction "PA05_10") (pintype "bidirectional"))
    )
    (net (code "126") (name "PHOTO3") (class "Default")
      (node (ref "Q18") (pin "E") (pinfunction "E_E") (pintype "passive"))
      (node (ref "R32") (pin "P$2") (pinfunction "P$2_P$2") (pintype "passive"))
      (node (ref "U1") (pin "11") (pinfunction "PA06_11") (pintype "bidirectional"))
    )
    (net (code "127") (name "PHOTO4") (class "Default")
      (node (ref "Q19") (pin "E") (pinfunction "E_E") (pintype "passive"))
      (node (ref "R33") (pin "P$2") (pinfunction "P$2_P$2") (pintype "passive"))
      (node (ref "U1") (pin "12") (pinfunction "PA07_12") (pintype "bidirectional"))
    )
    (net (code "128") (name "PHOTO5") (class "Default")
      (node (ref "Q24") (pin "E") (pinfunction "E_E") (pintype "passive"))
      (node (ref "R38") (pin "P$2") (pinfunction "P$2_P$2") (pintype "passive"))
      (node (ref "U1") (pin "13") (pinfunction "PA08_13") (pintype "bidirectional"))
    )
    (net (code "129") (name "PHOTO6") (class "Default")
      (node (ref "Q25") (pin "E") (pinfunction "E_E") (pintype "passive"))
      (node (ref "R39") (pin "P$2") (pinfunction "P$2_P$2") (pintype "passive"))
      (node (ref "U1") (pin "14") (pinfunction "PA09_14") (pintype "bidirectional"))
    )
    (net (code "130") (name "PHOTO7") (class "Default")
      (node (ref "Q26") (pin "E") (pinfunction "E_E") (pintype "passive"))
      (node (ref "R40") (pin "2") (pinfunction "P$2_2") (pintype "passive"))
      (node (ref "U1") (pin "15") (pinfunction "PA10_15") (pintype "bidirectional"))
    )
    (net (code "131") (name "PHOTO8") (class "Default")
      (node (ref "Q27") (pin "E") (pinfunction "E_E") (pintype "passive"))
      (node (ref "R41") (pin "P$2") (pinfunction "P$2_P$2") (pintype "passive"))
      (node (ref "U1") (pin "8") (pinfunction "PB09_8") (pintype "bidirectional"))
    )
    (net (code "132") (name "SCL") (class "Default")
      (node (ref "R50") (pin "1") (pinfunction "P$1_1") (pintype "passive"))
      (node (ref "TP2") (pin "P1") (pinfunction "P$1_P1") (pintype "passive"))
      (node (ref "U1") (pin "32") (pinfunction "PA23_32") (pintype "bidirectional"))
      (node (ref "U11") (pin "19") (pinfunction "SCL_19") (pintype "input"))
      (node (ref "U12") (pin "12") (pinfunction "SCL_12") (pintype "input"))
      (node (ref "U4") (pin "19") (pinfunction "COM1_19") (pintype "bidirectional"))
    )
    (net (code "133") (name "SDA") (class "Default")
      (node (ref "R51") (pin "1") (pinfunction "P$1_1") (pintype "passive"))
      (node (ref "TP1") (pin "P1") (pinfunction "P$1_P1") (pintype "passive"))
      (node (ref "U1") (pin "31") (pinfunction "PA22_31") (pintype "bidirectional"))
      (node (ref "U11") (pin "20") (pinfunction "SDA_20") (pintype "bidirectional"))
      (node (ref "U12") (pin "13") (pinfunction "SDA_13") (pintype "bidirectional"))
      (node (ref "U4") (pin "20") (pinfunction "COM0_20") (pintype "bidirectional"))
    )
    (net (code "134") (name "SWDCLK") (class "Default")
      (node (ref "J1") (pin "P9") (pinfunction "9_P9") (pintype "passive"))
      (node (ref "R5") (pin "1") (pinfunction "P$1_1") (pintype "passive"))
      (node (ref "U1") (pin "45") (pinfunction "PA30_45") (pintype "bidirectional"))
    )
    (net (code "135") (name "SWDIO") (class "Default")
      (node (ref "J1") (pin "P10") (pinfunction "10_P10") (pintype "passive"))
      (node (ref "U1") (pin "46") (pinfunction "PA31_46") (pintype "bidirectional"))
    )
    (net (code "136") (name "VREFA") (class "Default")
      (node (ref "C79") (pin "2") (pinfunction "P$2_2") (pintype "passive"))
      (node (ref "FB2") (pin "2") (pinfunction "P$2_2") (pintype "passive"))
      (node (ref "U1") (pin "4") (pinfunction "PA03_4") (pintype "bidirectional"))
    )
    (net (code "137") (name "XIN") (class "Default")
      (node (ref "C14") (pin "2") (pinfunction "P$2_2") (pintype "passive"))
      (node (ref "U1") (pin "23") (pinfunction "PA14_23") (pintype "bidirectional"))
      (node (ref "XTAL2") (pin "2") (pinfunction "P$2_2") (pintype "passive"))
      (node (ref "XTAL2") (pin "4") (pinfunction "P$2_4") (pintype "passive"))
    )
    (net (code "138") (name "XIN32") (class "Default")
      (node (ref "C11") (pin "2") (pinfunction "P$2_2") (pintype "passive"))
      (node (ref "U1") (pin "1") (pinfunction "PA00_1") (pintype "bidirectional"))
      (node (ref "XTAL1") (pin "1") (pinfunction "P$1_1") (pintype "passive"))
    )
    (net (code "139") (name "XOUT") (class "Default")
      (node (ref "C13") (pin "2") (pinfunction "P$2_2") (pintype "passive"))
      (node (ref "U1") (pin "24") (pinfunction "PA15_24") (pintype "bidirectional"))
      (node (ref "XTAL2") (pin "1") (pinfunction "P$1_1") (pintype "passive"))
      (node (ref "XTAL2") (pin "3") (pinfunction "P$1_3") (pintype "passive"))
    )
    (net (code "140") (name "XOUT32") (class "Default")
      (node (ref "C12") (pin "2") (pinfunction "P$2_2") (pintype "passive"))
      (node (ref "U1") (pin "2") (pinfunction "PA01_2") (pintype "bidirectional"))
      (node (ref "XTAL1") (pin "2") (pinfunction "P$2_2") (pintype "passive"))
    )
    (net (code "141") (name "unconnected-(J1-4-PadP4)") (class "Default")
      (node (ref "J1") (pin "P4") (pinfunction "4_P4") (pintype "passive"))
    )
    (net (code "142") (name "unconnected-(J1-5-PadP5)") (class "Default")
      (node (ref "J1") (pin "P5") (pinfunction "5_P5") (pintype "passive"))
    )
    (net (code "143") (name "unconnected-(J1-7-PadP7)") (class "Default")
      (node (ref "J1") (pin "P7") (pinfunction "7_P7") (pintype "passive"))
    )
    (net (code "144") (name "unconnected-(J1-8-PadP8)") (class "Default")
      (node (ref "J1") (pin "P8") (pinfunction "8_P8") (pintype "passive"))
    )
    (net (code "145") (name "unconnected-(S2-Pad1)") (class "Default")
      (node (ref "S2") (pin "1") (pinfunction "1_1") (pintype "passive"))
    )
    (net (code "146") (name "unconnected-(U1-PA02-Pad3)") (class "Default")
      (node (ref "U1") (pin "3") (pinfunction "PA02_3") (pintype "bidirectional"))
    )
    (net (code "147") (name "unconnected-(U1-PA25-Pad34)") (class "Default")
      (node (ref "U1") (pin "34") (pinfunction "PA25_34") (pintype "bidirectional"))
    )
    (net (code "148") (name "unconnected-(U1-PA27-Pad39)") (class "Default")
      (node (ref "U1") (pin "39") (pinfunction "PA27_39") (pintype "bidirectional"))
    )
    (net (code "149") (name "unconnected-(U1-PA28-Pad41)") (class "Default")
      (node (ref "U1") (pin "41") (pinfunction "PA28_41") (pintype "bidirectional"))
    )
    (net (code "150") (name "unconnected-(U1-PB02-Pad47)") (class "Default")
      (node (ref "U1") (pin "47") (pinfunction "PB02_47") (pintype "bidirectional"))
    )
    (net (code "151") (name "unconnected-(U1-PB03-Pad48)") (class "Default")
      (node (ref "U1") (pin "48") (pinfunction "PB03_48") (pintype "bidirectional"))
    )
    (net (code "152") (name "unconnected-(U1-PB08-Pad7)") (class "Default")
      (node (ref "U1") (pin "7") (pinfunction "PB08_7") (pintype "bidirectional"))
    )
    (net (code "153") (name "unconnected-(U1-PB11-Pad20)") (class "Default")
      (node (ref "U1") (pin "20") (pinfunction "PB11_20") (pintype "bidirectional"))
    )
    (net (code "154") (name "unconnected-(U4-BL_IND-Pad10)") (class "Default")
      (node (ref "U4") (pin "10") (pinfunction "BL_IND_10") (pintype "output"))
    )
    (net (code "155") (name "unconnected-(U11-P0_5-Pad6)") (class "Default")
      (node (ref "U11") (pin "6") (pinfunction "P0_5_6") (pintype "bidirectional"))
    )
    (net (code "156") (name "unconnected-(U11-P0_6-Pad7)") (class "Default")
      (node (ref "U11") (pin "7") (pinfunction "P0_6_7") (pintype "bidirectional"))
    )
    (net (code "157") (name "unconnected-(U11-P0_7-Pad8)") (class "Default")
      (node (ref "U11") (pin "8") (pinfunction "P0_7_8") (pintype "bidirectional"))
    )
    (net (code "158") (name "unconnected-(U11-~{INT}-Pad22)") (class "Default")
      (node (ref "U11") (pin "22") (pinfunction "~{INT}_22") (pintype "output"))
    )
    (net (code "159") (name "unconnected-(U12-~{INT}-Pad11)") (class "Default")
      (node (ref "U12") (pin "11") (pinfunction "~{INT}_11") (pintype "output"))
    )
    (net (code "160") (name "~{RESET}") (class "Default")
      (node (ref "C7") (pin "1") (pinfunction "P$1_1") (pintype "passive"))
      (node (ref "J1") (pin "P6") (pinfunction "6_P6") (pintype "passive"))
      (node (ref "R1") (pin "1") (pinfunction "P$1_1") (pintype "passive"))
      (node (ref "R2") (pin "P$2") (pinfunction "P$2_P$2") (pintype "passive"))
      (node (ref "U1") (pin "40") (pinfunction "~{RESET}_40") (pintype "input"))
    )
  )
)
